# 56_ch_sample-and-hold_card_v1_1.net
KiCad netlist of a schematic drawn in EAGLE
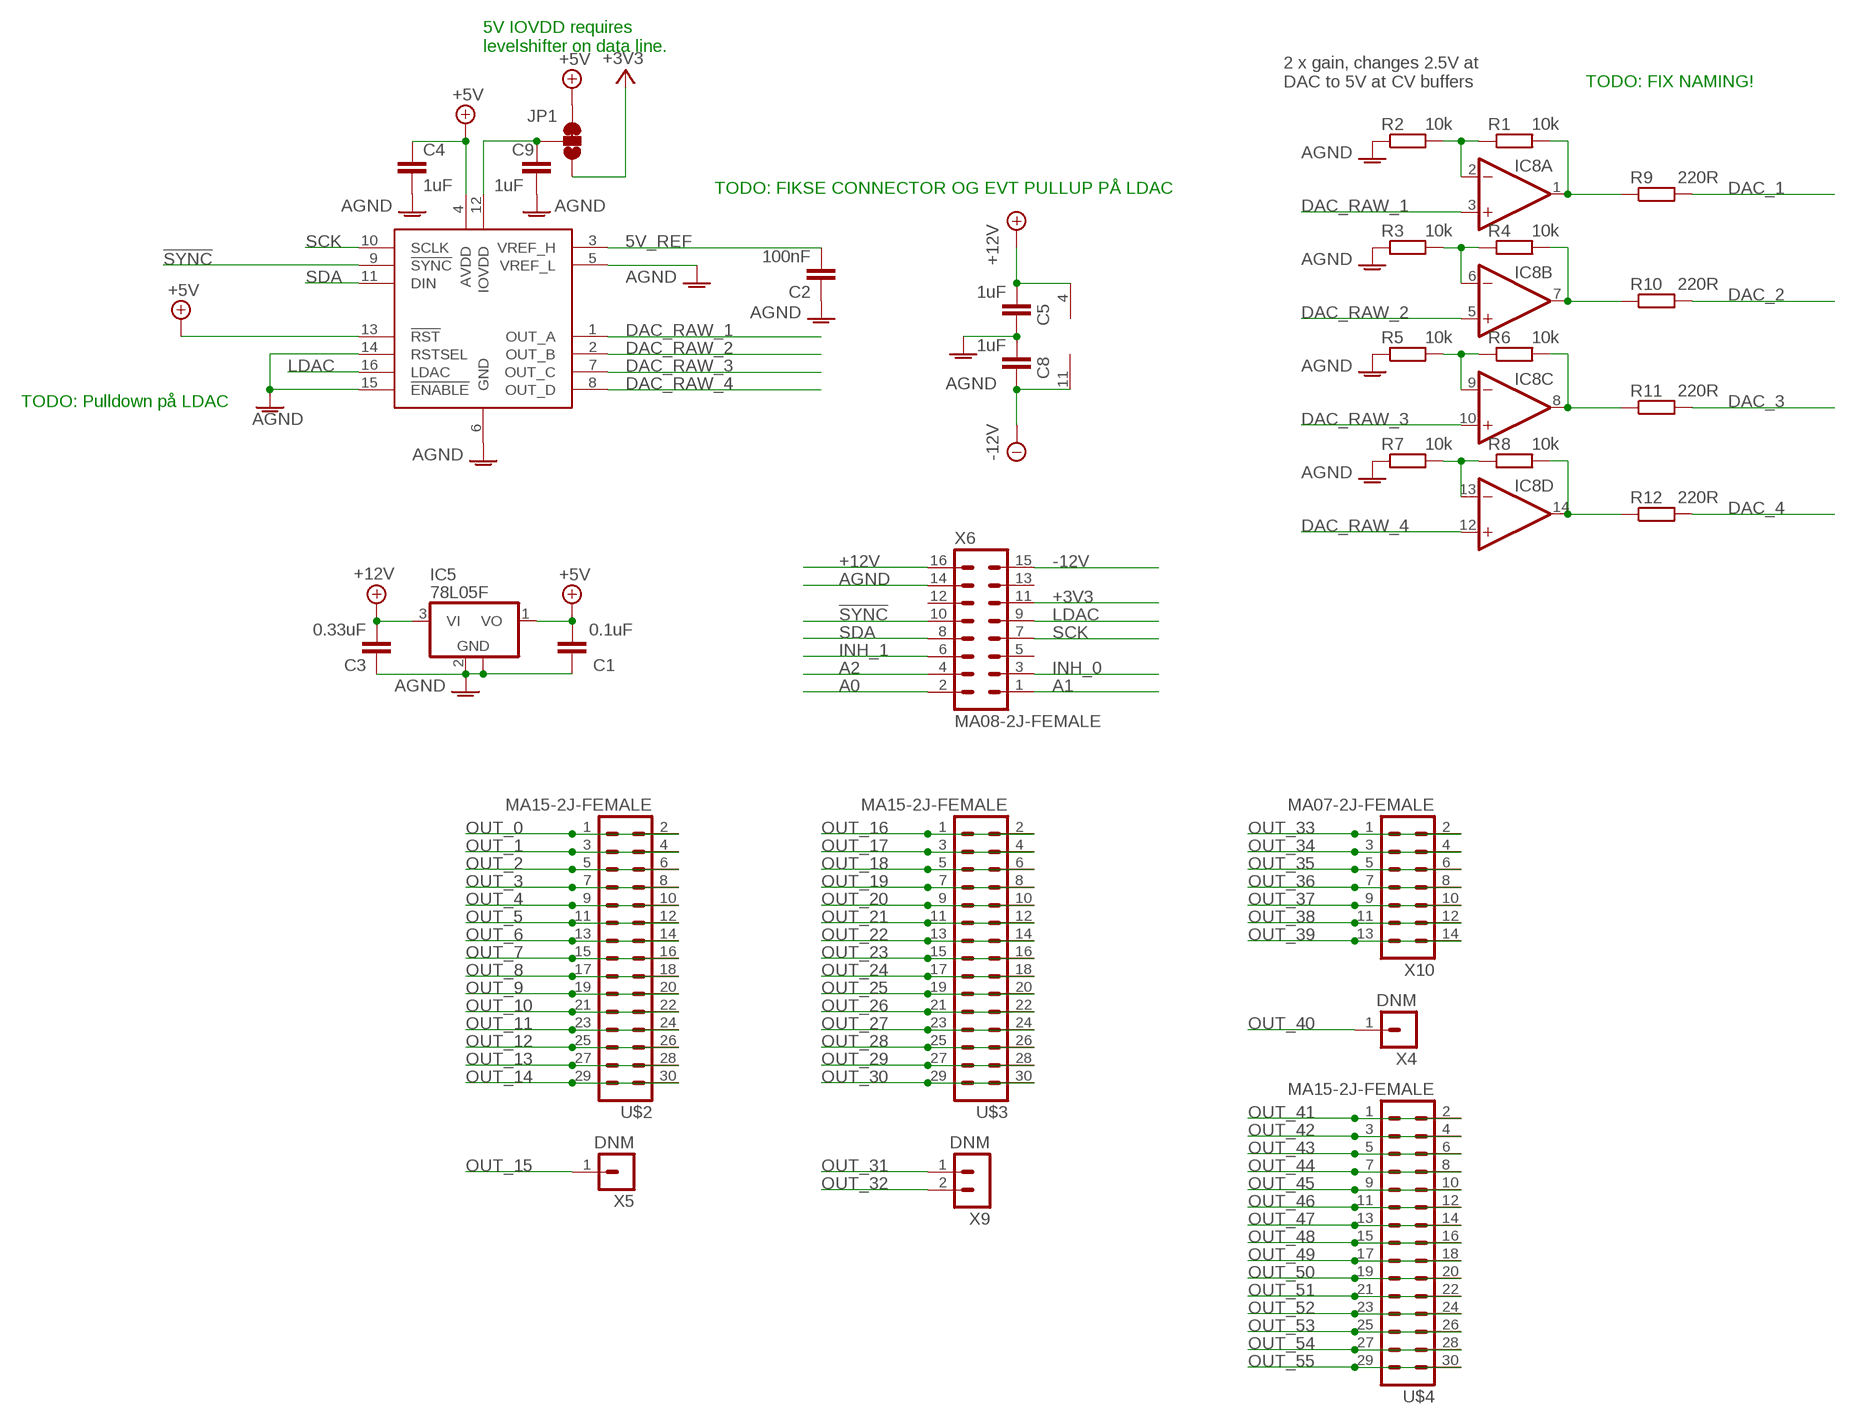
[diagram p0: schematic, sheet 1]
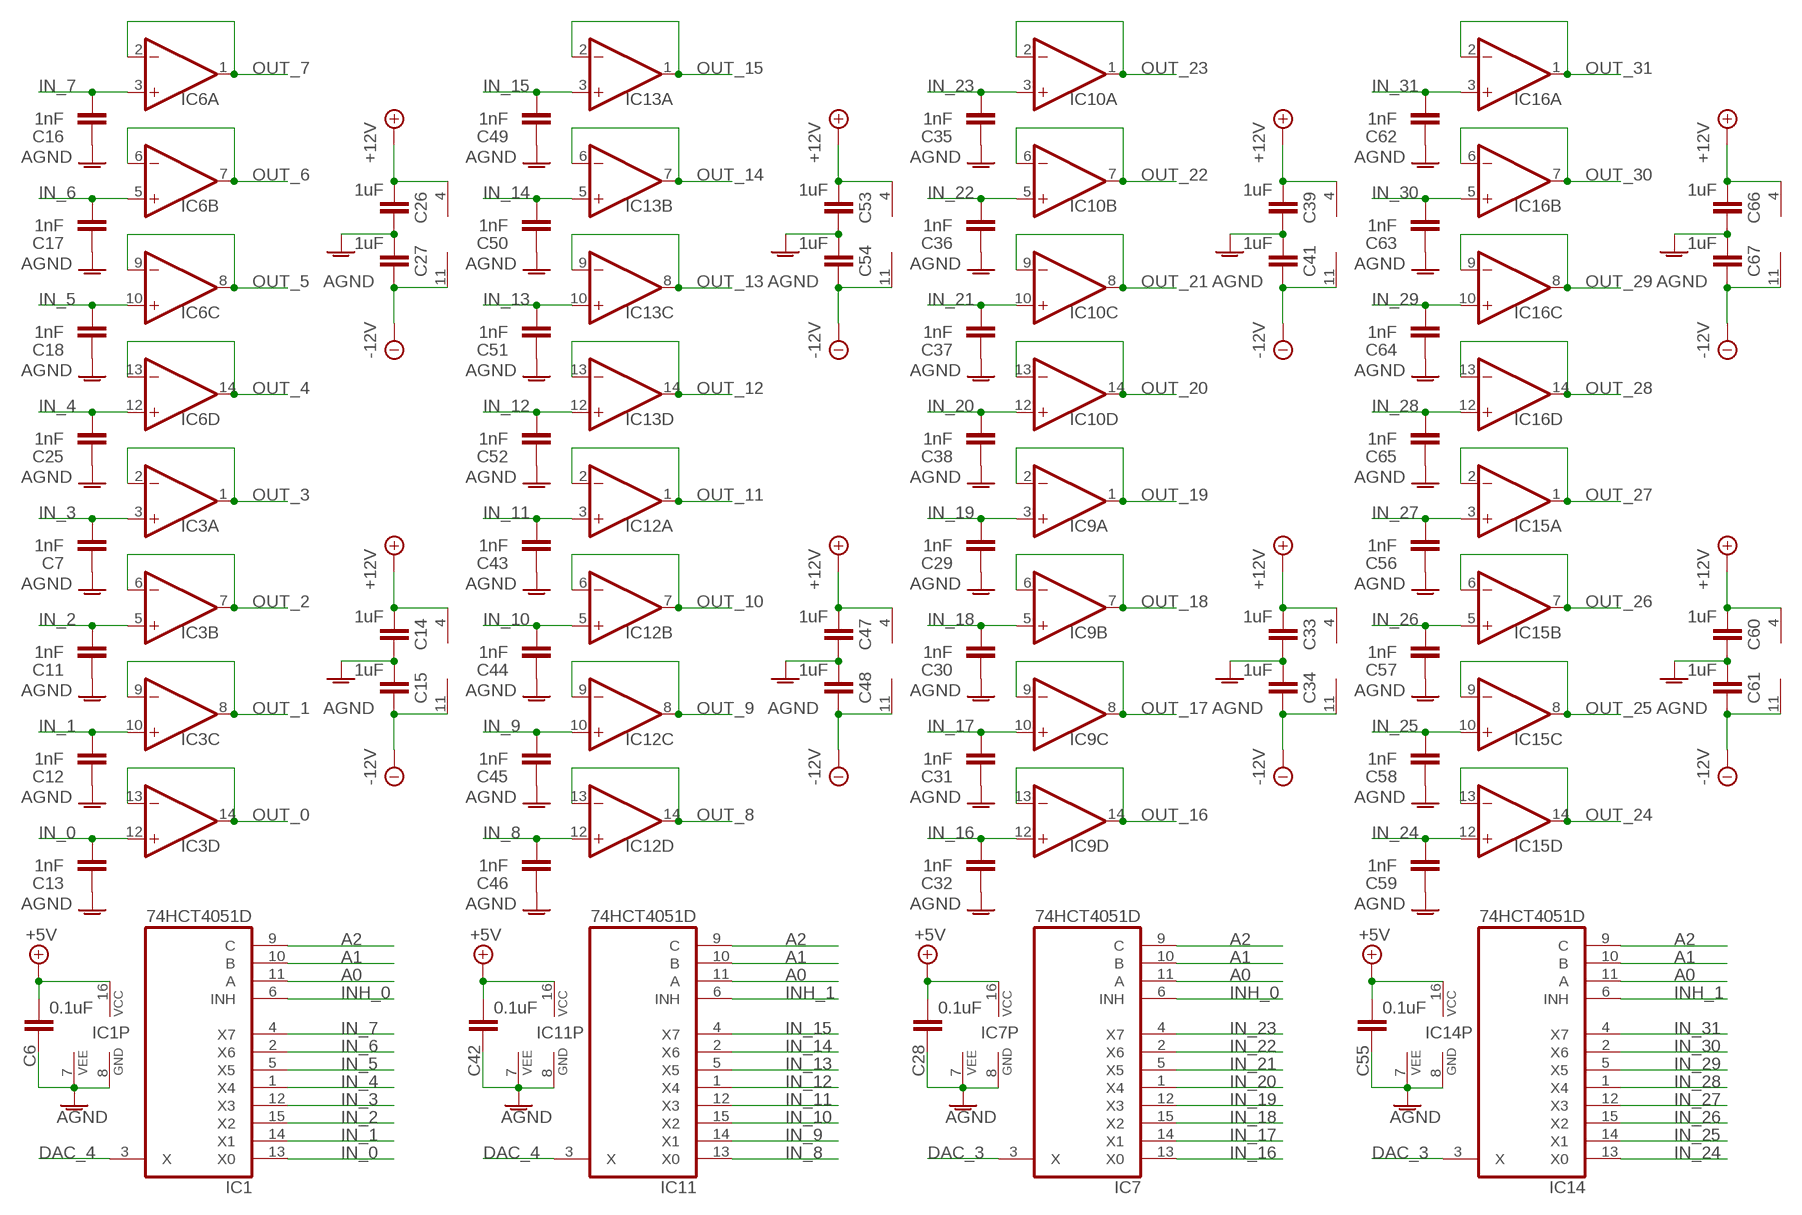
[diagram p1: schematic, sheet 2]
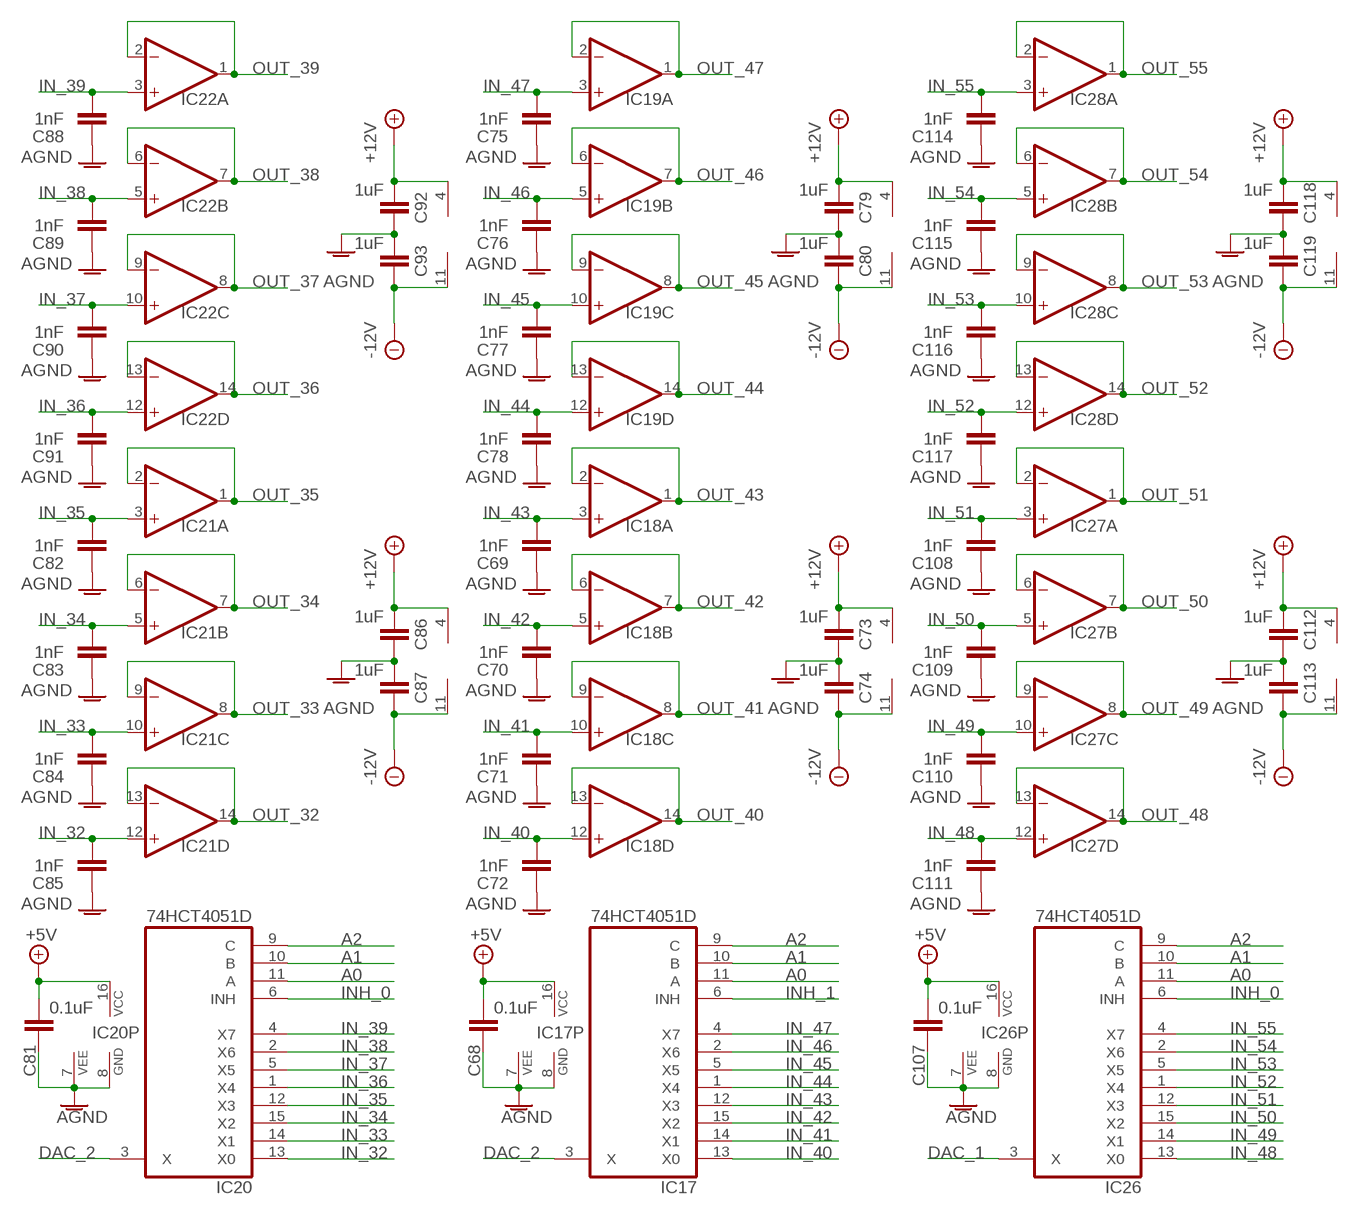
[diagram p2: schematic, sheet 3]

(export (version "E")
  (design (tool "Eeschema 10.0.6"))
  (components
    (comp (ref "C1")
      (value "0.1uF")
      (footprint "eagle-import:C0603")
      (libsource (lib "eagle-import") (part "C-EUC0603"))
    )
    (comp (ref "C2")
      (value "100nF")
      (footprint "eagle-import:C0603")
      (libsource (lib "eagle-import") (part "C-EUC0603"))
    )
    (comp (ref "C3")
      (value "0.33uF")
      (footprint "eagle-import:C0603")
      (libsource (lib "eagle-import") (part "C-EUC0603"))
    )
    (comp (ref "C4")
      (value "1uF")
      (footprint "eagle-import:C0402-J")
      (libsource (lib "eagle-import") (part "C-EU-J0402"))
    )
    (comp (ref "C5")
      (value "1uF")
      (footprint "eagle-import:C0402-J")
      (libsource (lib "eagle-import") (part "C-EU-J0402"))
    )
    (comp (ref "C8")
      (value "1uF")
      (footprint "eagle-import:C0402-J")
      (libsource (lib "eagle-import") (part "C-EU-J0402"))
    )
    (comp (ref "C9")
      (value "1uF")
      (footprint "eagle-import:C0402-J")
      (libsource (lib "eagle-import") (part "C-EU-J0402"))
    )
    (comp (ref "IC2")
      (value "DAC8565F")
      (footprint "eagle-import:DIL16-FM-CON")
      (libsource (lib "eagle-import") (part "DAC8565F"))
    )
    (comp (ref "IC5")
      (value "78L05F")
      (footprint "eagle-import:SOT89")
      (libsource (lib "eagle-import") (part "78LF05"))
    )
    (comp (ref "IC8")
      (value "TL074JT")
      (footprint "eagle-import:TSSOP14J")
      (libsource (lib "eagle-import") (part "TL074JT"))
    )
    (comp (ref "JP1")
      (value "JUMPER-SMT_3_1-NC_TRACE_NO-SILK_DNM")
      (footprint "eagle-import:SMT-JUMPER_3_1-NC_TRACE_NO-SILK")
      (libsource (lib "eagle-import") (part "JUMPER-SMT_3_1-NC_TRACE_NO-SILK"))
    )
    (comp (ref "R1")
      (value "10k")
      (footprint "eagle-import:R0603")
      (libsource (lib "eagle-import") (part "R-EU_R0603"))
    )
    (comp (ref "R2")
      (value "10k")
      (footprint "eagle-import:R0603")
      (libsource (lib "eagle-import") (part "R-EU_R0603"))
    )
    (comp (ref "R3")
      (value "10k")
      (footprint "eagle-import:R0603")
      (libsource (lib "eagle-import") (part "R-EU_R0603"))
    )
    (comp (ref "R4")
      (value "10k")
      (footprint "eagle-import:R0603")
      (libsource (lib "eagle-import") (part "R-EU_R0603"))
    )
    (comp (ref "R5")
      (value "10k")
      (footprint "eagle-import:R0603")
      (libsource (lib "eagle-import") (part "R-EU_R0603"))
    )
    (comp (ref "R6")
      (value "10k")
      (footprint "eagle-import:R0603")
      (libsource (lib "eagle-import") (part "R-EU_R0603"))
    )
    (comp (ref "R7")
      (value "10k")
      (footprint "eagle-import:R0603")
      (libsource (lib "eagle-import") (part "R-EU_R0603"))
    )
    (comp (ref "R8")
      (value "10k")
      (footprint "eagle-import:R0603")
      (libsource (lib "eagle-import") (part "R-EU_R0603"))
    )
    (comp (ref "R9")
      (value "220R")
      (footprint "eagle-import:R0603")
      (libsource (lib "eagle-import") (part "R-EU_R0603"))
    )
    (comp (ref "R10")
      (value "220R")
      (footprint "eagle-import:R0603")
      (libsource (lib "eagle-import") (part "R-EU_R0603"))
    )
    (comp (ref "R11")
      (value "220R")
      (footprint "eagle-import:R0603")
      (libsource (lib "eagle-import") (part "R-EU_R0603"))
    )
    (comp (ref "R12")
      (value "220R")
      (footprint "eagle-import:R0603")
      (libsource (lib "eagle-import") (part "R-EU_R0603"))
    )
    (comp (ref "U$2")
      (value "MA15-2J-FEMALE")
      (footprint "eagle-import:MA15-2J")
      (libsource (lib "eagle-import") (part "MA15-2J"))
    )
    (comp (ref "U$3")
      (value "MA15-2J-FEMALE")
      (footprint "eagle-import:MA15-2J")
      (libsource (lib "eagle-import") (part "MA15-2J"))
    )
    (comp (ref "U$4")
      (value "MA15-2J-FEMALE")
      (footprint "eagle-import:MA15-2J")
      (libsource (lib "eagle-import") (part "MA15-2J"))
    )
    (comp (ref "X4")
      (value "DNM")
      (footprint "eagle-import:MA01N-1J")
      (libsource (lib "eagle-import") (part "MA01-1JN"))
    )
    (comp (ref "X5")
      (value "DNM")
      (footprint "eagle-import:MA01N-1J")
      (libsource (lib "eagle-import") (part "MA01-1JN"))
    )
    (comp (ref "X6")
      (value "MA08-2J-FEMALE")
      (footprint "eagle-import:MA08-2J")
      (libsource (lib "eagle-import") (part "MA08-2J"))
    )
    (comp (ref "X9")
      (value "DNM")
      (footprint "eagle-import:MA02N-1J")
      (libsource (lib "eagle-import") (part "MA02-1JN"))
    )
    (comp (ref "X10")
      (value "MA07-2J-FEMALE")
      (footprint "eagle-import:MA07-2J")
      (libsource (lib "eagle-import") (part "MA07-2J"))
    )
    (comp (ref "C6")
      (value "0.1uF")
      (footprint "eagle-import:C0402-J")
      (libsource (lib "eagle-import") (part "C-EU-J0402"))
    )
    (comp (ref "C7")
      (value "1nF")
      (footprint "eagle-import:C0603-J")
      (libsource (lib "eagle-import") (part "C-EU-J0603"))
    )
    (comp (ref "C11")
      (value "1nF")
      (footprint "eagle-import:C0603-J")
      (libsource (lib "eagle-import") (part "C-EU-J0603"))
    )
    (comp (ref "C12")
      (value "1nF")
      (footprint "eagle-import:C0603-J")
      (libsource (lib "eagle-import") (part "C-EU-J0603"))
    )
    (comp (ref "C13")
      (value "1nF")
      (footprint "eagle-import:C0603-J")
      (libsource (lib "eagle-import") (part "C-EU-J0603"))
    )
    (comp (ref "C14")
      (value "1uF")
      (footprint "eagle-import:C0402-J")
      (libsource (lib "eagle-import") (part "C-EU-J0402"))
    )
    (comp (ref "C15")
      (value "1uF")
      (footprint "eagle-import:C0402-J")
      (libsource (lib "eagle-import") (part "C-EU-J0402"))
    )
    (comp (ref "C16")
      (value "1nF")
      (footprint "eagle-import:C0603-J")
      (libsource (lib "eagle-import") (part "C-EU-J0603"))
    )
    (comp (ref "C17")
      (value "1nF")
      (footprint "eagle-import:C0603-J")
      (libsource (lib "eagle-import") (part "C-EU-J0603"))
    )
    (comp (ref "C18")
      (value "1nF")
      (footprint "eagle-import:C0603-J")
      (libsource (lib "eagle-import") (part "C-EU-J0603"))
    )
    (comp (ref "C25")
      (value "1nF")
      (footprint "eagle-import:C0603-J")
      (libsource (lib "eagle-import") (part "C-EU-J0603"))
    )
    (comp (ref "C26")
      (value "1uF")
      (footprint "eagle-import:C0402-J")
      (libsource (lib "eagle-import") (part "C-EU-J0402"))
    )
    (comp (ref "C27")
      (value "1uF")
      (footprint "eagle-import:C0402-J")
      (libsource (lib "eagle-import") (part "C-EU-J0402"))
    )
    (comp (ref "C28")
      (value "0.1uF")
      (footprint "eagle-import:C0402-J")
      (libsource (lib "eagle-import") (part "C-EU-J0402"))
    )
    (comp (ref "C29")
      (value "1nF")
      (footprint "eagle-import:C0603-J")
      (libsource (lib "eagle-import") (part "C-EU-J0603"))
    )
    (comp (ref "C30")
      (value "1nF")
      (footprint "eagle-import:C0603-J")
      (libsource (lib "eagle-import") (part "C-EU-J0603"))
    )
    (comp (ref "C31")
      (value "1nF")
      (footprint "eagle-import:C0603-J")
      (libsource (lib "eagle-import") (part "C-EU-J0603"))
    )
    (comp (ref "C32")
      (value "1nF")
      (footprint "eagle-import:C0603-J")
      (libsource (lib "eagle-import") (part "C-EU-J0603"))
    )
    (comp (ref "C33")
      (value "1uF")
      (footprint "eagle-import:C0402-J")
      (libsource (lib "eagle-import") (part "C-EU-J0402"))
    )
    (comp (ref "C34")
      (value "1uF")
      (footprint "eagle-import:C0402-J")
      (libsource (lib "eagle-import") (part "C-EU-J0402"))
    )
    (comp (ref "C35")
      (value "1nF")
      (footprint "eagle-import:C0603-J")
      (libsource (lib "eagle-import") (part "C-EU-J0603"))
    )
    (comp (ref "C36")
      (value "1nF")
      (footprint "eagle-import:C0603-J")
      (libsource (lib "eagle-import") (part "C-EU-J0603"))
    )
    (comp (ref "C37")
      (value "1nF")
      (footprint "eagle-import:C0603-J")
      (libsource (lib "eagle-import") (part "C-EU-J0603"))
    )
    (comp (ref "C38")
      (value "1nF")
      (footprint "eagle-import:C0603-J")
      (libsource (lib "eagle-import") (part "C-EU-J0603"))
    )
    (comp (ref "C39")
      (value "1uF")
      (footprint "eagle-import:C0402-J")
      (libsource (lib "eagle-import") (part "C-EU-J0402"))
    )
    (comp (ref "C41")
      (value "1uF")
      (footprint "eagle-import:C0402-J")
      (libsource (lib "eagle-import") (part "C-EU-J0402"))
    )
    (comp (ref "C42")
      (value "0.1uF")
      (footprint "eagle-import:C0402-J")
      (libsource (lib "eagle-import") (part "C-EU-J0402"))
    )
    (comp (ref "C43")
      (value "1nF")
      (footprint "eagle-import:C0603-J")
      (libsource (lib "eagle-import") (part "C-EU-J0603"))
    )
    (comp (ref "C44")
      (value "1nF")
      (footprint "eagle-import:C0603-J")
      (libsource (lib "eagle-import") (part "C-EU-J0603"))
    )
    (comp (ref "C45")
      (value "1nF")
      (footprint "eagle-import:C0603-J")
      (libsource (lib "eagle-import") (part "C-EU-J0603"))
    )
    (comp (ref "C46")
      (value "1nF")
      (footprint "eagle-import:C0603-J")
      (libsource (lib "eagle-import") (part "C-EU-J0603"))
    )
    (comp (ref "C47")
      (value "1uF")
      (footprint "eagle-import:C0402-J")
      (libsource (lib "eagle-import") (part "C-EU-J0402"))
    )
    (comp (ref "C48")
      (value "1uF")
      (footprint "eagle-import:C0402-J")
      (libsource (lib "eagle-import") (part "C-EU-J0402"))
    )
    (comp (ref "C49")
      (value "1nF")
      (footprint "eagle-import:C0603-J")
      (libsource (lib "eagle-import") (part "C-EU-J0603"))
    )
    (comp (ref "C50")
      (value "1nF")
      (footprint "eagle-import:C0603-J")
      (libsource (lib "eagle-import") (part "C-EU-J0603"))
    )
    (comp (ref "C51")
      (value "1nF")
      (footprint "eagle-import:C0603-J")
      (libsource (lib "eagle-import") (part "C-EU-J0603"))
    )
    (comp (ref "C52")
      (value "1nF")
      (footprint "eagle-import:C0603-J")
      (libsource (lib "eagle-import") (part "C-EU-J0603"))
    )
    (comp (ref "C53")
      (value "1uF")
      (footprint "eagle-import:C0402-J")
      (libsource (lib "eagle-import") (part "C-EU-J0402"))
    )
    (comp (ref "C54")
      (value "1uF")
      (footprint "eagle-import:C0402-J")
      (libsource (lib "eagle-import") (part "C-EU-J0402"))
    )
    (comp (ref "C55")
      (value "0.1uF")
      (footprint "eagle-import:C0402-J")
      (libsource (lib "eagle-import") (part "C-EU-J0402"))
    )
    (comp (ref "C56")
      (value "1nF")
      (footprint "eagle-import:C0603-J")
      (libsource (lib "eagle-import") (part "C-EU-J0603"))
    )
    (comp (ref "C57")
      (value "1nF")
      (footprint "eagle-import:C0603-J")
      (libsource (lib "eagle-import") (part "C-EU-J0603"))
    )
    (comp (ref "C58")
      (value "1nF")
      (footprint "eagle-import:C0603-J")
      (libsource (lib "eagle-import") (part "C-EU-J0603"))
    )
    (comp (ref "C59")
      (value "1nF")
      (footprint "eagle-import:C0603-J")
      (libsource (lib "eagle-import") (part "C-EU-J0603"))
    )
    (comp (ref "C60")
      (value "1uF")
      (footprint "eagle-import:C0402-J")
      (libsource (lib "eagle-import") (part "C-EU-J0402"))
    )
    (comp (ref "C61")
      (value "1uF")
      (footprint "eagle-import:C0402-J")
      (libsource (lib "eagle-import") (part "C-EU-J0402"))
    )
    (comp (ref "C62")
      (value "1nF")
      (footprint "eagle-import:C0603-J")
      (libsource (lib "eagle-import") (part "C-EU-J0603"))
    )
    (comp (ref "C63")
      (value "1nF")
      (footprint "eagle-import:C0603-J")
      (libsource (lib "eagle-import") (part "C-EU-J0603"))
    )
    (comp (ref "C64")
      (value "1nF")
      (footprint "eagle-import:C0603-J")
      (libsource (lib "eagle-import") (part "C-EU-J0603"))
    )
    (comp (ref "C65")
      (value "1nF")
      (footprint "eagle-import:C0603-J")
      (libsource (lib "eagle-import") (part "C-EU-J0603"))
    )
    (comp (ref "C66")
      (value "1uF")
      (footprint "eagle-import:C0402-J")
      (libsource (lib "eagle-import") (part "C-EU-J0402"))
    )
    (comp (ref "C67")
      (value "1uF")
      (footprint "eagle-import:C0402-J")
      (libsource (lib "eagle-import") (part "C-EU-J0402"))
    )
    (comp (ref "IC1")
      (value "74HCT4051D")
      (footprint "eagle-import:SO16")
      (libsource (lib "eagle-import") (part "4051D"))
    )
    (comp (ref "IC3")
      (value "TL074JT")
      (footprint "eagle-import:TSSOP14J")
      (libsource (lib "eagle-import") (part "TL074JT"))
    )
    (comp (ref "IC6")
      (value "TL074JT")
      (footprint "eagle-import:TSSOP14J")
      (libsource (lib "eagle-import") (part "TL074JT"))
    )
    (comp (ref "IC7")
      (value "74HCT4051D")
      (footprint "eagle-import:SO16")
      (libsource (lib "eagle-import") (part "4051D"))
    )
    (comp (ref "IC9")
      (value "TL074JT")
      (footprint "eagle-import:TSSOP14J")
      (libsource (lib "eagle-import") (part "TL074JT"))
    )
    (comp (ref "IC10")
      (value "TL074JT")
      (footprint "eagle-import:TSSOP14J")
      (libsource (lib "eagle-import") (part "TL074JT"))
    )
    (comp (ref "IC11")
      (value "74HCT4051D")
      (footprint "eagle-import:SO16")
      (libsource (lib "eagle-import") (part "4051D"))
    )
    (comp (ref "IC12")
      (value "TL074JT")
      (footprint "eagle-import:TSSOP14J")
      (libsource (lib "eagle-import") (part "TL074JT"))
    )
    (comp (ref "IC13")
      (value "TL074JT")
      (footprint "eagle-import:TSSOP14J")
      (libsource (lib "eagle-import") (part "TL074JT"))
    )
    (comp (ref "IC14")
      (value "74HCT4051D")
      (footprint "eagle-import:SO16")
      (libsource (lib "eagle-import") (part "4051D"))
    )
    (comp (ref "IC15")
      (value "TL074JT")
      (footprint "eagle-import:TSSOP14J")
      (libsource (lib "eagle-import") (part "TL074JT"))
    )
    (comp (ref "IC16")
      (value "TL074JT")
      (footprint "eagle-import:TSSOP14J")
      (libsource (lib "eagle-import") (part "TL074JT"))
    )
    (comp (ref "C68")
      (value "0.1uF")
      (footprint "eagle-import:C0402-J")
      (libsource (lib "eagle-import") (part "C-EU-J0402"))
    )
    (comp (ref "C69")
      (value "1nF")
      (footprint "eagle-import:C0603-J")
      (libsource (lib "eagle-import") (part "C-EU-J0603"))
    )
    (comp (ref "C70")
      (value "1nF")
      (footprint "eagle-import:C0603-J")
      (libsource (lib "eagle-import") (part "C-EU-J0603"))
    )
    (comp (ref "C71")
      (value "1nF")
      (footprint "eagle-import:C0603-J")
      (libsource (lib "eagle-import") (part "C-EU-J0603"))
    )
    (comp (ref "C72")
      (value "1nF")
      (footprint "eagle-import:C0603-J")
      (libsource (lib "eagle-import") (part "C-EU-J0603"))
    )
    (comp (ref "C73")
      (value "1uF")
      (footprint "eagle-import:C0402-J")
      (libsource (lib "eagle-import") (part "C-EU-J0402"))
    )
    (comp (ref "C74")
      (value "1uF")
      (footprint "eagle-import:C0402-J")
      (libsource (lib "eagle-import") (part "C-EU-J0402"))
    )
    (comp (ref "C75")
      (value "1nF")
      (footprint "eagle-import:C0603-J")
      (libsource (lib "eagle-import") (part "C-EU-J0603"))
    )
    (comp (ref "C76")
      (value "1nF")
      (footprint "eagle-import:C0603-J")
      (libsource (lib "eagle-import") (part "C-EU-J0603"))
    )
    (comp (ref "C77")
      (value "1nF")
      (footprint "eagle-import:C0603-J")
      (libsource (lib "eagle-import") (part "C-EU-J0603"))
    )
    (comp (ref "C78")
      (value "1nF")
      (footprint "eagle-import:C0603-J")
      (libsource (lib "eagle-import") (part "C-EU-J0603"))
    )
    (comp (ref "C79")
      (value "1uF")
      (footprint "eagle-import:C0402-J")
      (libsource (lib "eagle-import") (part "C-EU-J0402"))
    )
    (comp (ref "C80")
      (value "1uF")
      (footprint "eagle-import:C0402-J")
      (libsource (lib "eagle-import") (part "C-EU-J0402"))
    )
    (comp (ref "C81")
      (value "0.1uF")
      (footprint "eagle-import:C0402-J")
      (libsource (lib "eagle-import") (part "C-EU-J0402"))
    )
    (comp (ref "C82")
      (value "1nF")
      (footprint "eagle-import:C0603-J")
      (libsource (lib "eagle-import") (part "C-EU-J0603"))
    )
    (comp (ref "C83")
      (value "1nF")
      (footprint "eagle-import:C0603-J")
      (libsource (lib "eagle-import") (part "C-EU-J0603"))
    )
    (comp (ref "C84")
      (value "1nF")
      (footprint "eagle-import:C0603-J")
      (libsource (lib "eagle-import") (part "C-EU-J0603"))
    )
    (comp (ref "C85")
      (value "1nF")
      (footprint "eagle-import:C0603-J")
      (libsource (lib "eagle-import") (part "C-EU-J0603"))
    )
    (comp (ref "C86")
      (value "1uF")
      (footprint "eagle-import:C0402-J")
      (libsource (lib "eagle-import") (part "C-EU-J0402"))
    )
    (comp (ref "C87")
      (value "1uF")
      (footprint "eagle-import:C0402-J")
      (libsource (lib "eagle-import") (part "C-EU-J0402"))
    )
    (comp (ref "C88")
      (value "1nF")
      (footprint "eagle-import:C0603-J")
      (libsource (lib "eagle-import") (part "C-EU-J0603"))
    )
    (comp (ref "C89")
      (value "1nF")
      (footprint "eagle-import:C0603-J")
      (libsource (lib "eagle-import") (part "C-EU-J0603"))
    )
    (comp (ref "C90")
      (value "1nF")
      (footprint "eagle-import:C0603-J")
      (libsource (lib "eagle-import") (part "C-EU-J0603"))
    )
    (comp (ref "C91")
      (value "1nF")
      (footprint "eagle-import:C0603-J")
      (libsource (lib "eagle-import") (part "C-EU-J0603"))
    )
    (comp (ref "C92")
      (value "1uF")
      (footprint "eagle-import:C0402-J")
      (libsource (lib "eagle-import") (part "C-EU-J0402"))
    )
    (comp (ref "C93")
      (value "1uF")
      (footprint "eagle-import:C0402-J")
      (libsource (lib "eagle-import") (part "C-EU-J0402"))
    )
    (comp (ref "C107")
      (value "0.1uF")
      (footprint "eagle-import:C0402-J")
      (libsource (lib "eagle-import") (part "C-EU-J0402"))
    )
    (comp (ref "C108")
      (value "1nF")
      (footprint "eagle-import:C0603-J")
      (libsource (lib "eagle-import") (part "C-EU-J0603"))
    )
    (comp (ref "C109")
      (value "1nF")
      (footprint "eagle-import:C0603-J")
      (libsource (lib "eagle-import") (part "C-EU-J0603"))
    )
    (comp (ref "C110")
      (value "1nF")
      (footprint "eagle-import:C0603-J")
      (libsource (lib "eagle-import") (part "C-EU-J0603"))
    )
    (comp (ref "C111")
      (value "1nF")
      (footprint "eagle-import:C0603-J")
      (libsource (lib "eagle-import") (part "C-EU-J0603"))
    )
    (comp (ref "C112")
      (value "1uF")
      (footprint "eagle-import:C0402-J")
      (libsource (lib "eagle-import") (part "C-EU-J0402"))
    )
    (comp (ref "C113")
      (value "1uF")
      (footprint "eagle-import:C0402-J")
      (libsource (lib "eagle-import") (part "C-EU-J0402"))
    )
    (comp (ref "C114")
      (value "1nF")
      (footprint "eagle-import:C0603-J")
      (libsource (lib "eagle-import") (part "C-EU-J0603"))
    )
    (comp (ref "C115")
      (value "1nF")
      (footprint "eagle-import:C0603-J")
      (libsource (lib "eagle-import") (part "C-EU-J0603"))
    )
    (comp (ref "C116")
      (value "1nF")
      (footprint "eagle-import:C0603-J")
      (libsource (lib "eagle-import") (part "C-EU-J0603"))
    )
    (comp (ref "C117")
      (value "1nF")
      (footprint "eagle-import:C0603-J")
      (libsource (lib "eagle-import") (part "C-EU-J0603"))
    )
    (comp (ref "C118")
      (value "1uF")
      (footprint "eagle-import:C0402-J")
      (libsource (lib "eagle-import") (part "C-EU-J0402"))
    )
    (comp (ref "C119")
      (value "1uF")
      (footprint "eagle-import:C0402-J")
      (libsource (lib "eagle-import") (part "C-EU-J0402"))
    )
    (comp (ref "IC17")
      (value "74HCT4051D")
      (footprint "eagle-import:SO16")
      (libsource (lib "eagle-import") (part "4051D"))
    )
    (comp (ref "IC18")
      (value "TL074JT")
      (footprint "eagle-import:TSSOP14J")
      (libsource (lib "eagle-import") (part "TL074JT"))
    )
    (comp (ref "IC19")
      (value "TL074JT")
      (footprint "eagle-import:TSSOP14J")
      (libsource (lib "eagle-import") (part "TL074JT"))
    )
    (comp (ref "IC20")
      (value "74HCT4051D")
      (footprint "eagle-import:SO16")
      (libsource (lib "eagle-import") (part "4051D"))
    )
    (comp (ref "IC21")
      (value "TL074JT")
      (footprint "eagle-import:TSSOP14J")
      (libsource (lib "eagle-import") (part "TL074JT"))
    )
    (comp (ref "IC22")
      (value "TL074JT")
      (footprint "eagle-import:TSSOP14J")
      (libsource (lib "eagle-import") (part "TL074JT"))
    )
    (comp (ref "IC26")
      (value "74HCT4051D")
      (footprint "eagle-import:SO16")
      (libsource (lib "eagle-import") (part "4051D"))
    )
    (comp (ref "IC27")
      (value "TL074JT")
      (footprint "eagle-import:TSSOP14J")
      (libsource (lib "eagle-import") (part "TL074JT"))
    )
    (comp (ref "IC28")
      (value "TL074JT")
      (footprint "eagle-import:TSSOP14J")
      (libsource (lib "eagle-import") (part "TL074JT"))
    )
  )
  (nets
    (net (code "1") (name "+3V3") (class "Default")
      (node (ref "JP1") (pin "1") (pinfunction "1_1") (pintype "passive"))
      (node (ref "X6") (pin "11") (pinfunction "11_11") (pintype "passive"))
    )
    (net (code "2") (name "+5V") (class "Default")
      (node (ref "C1") (pin "2") (pinfunction "2_2") (pintype "passive"))
      (node (ref "C107") (pin "2") (pinfunction "2_2") (pintype "passive"))
      (node (ref "C28") (pin "2") (pinfunction "2_2") (pintype "passive"))
      (node (ref "C4") (pin "1") (pinfunction "1_1") (pintype "passive"))
      (node (ref "C42") (pin "2") (pinfunction "2_2") (pintype "passive"))
      (node (ref "C55") (pin "2") (pinfunction "2_2") (pintype "passive"))
      (node (ref "C6") (pin "2") (pinfunction "2_2") (pintype "passive"))
      (node (ref "C68") (pin "2") (pinfunction "2_2") (pintype "passive"))
      (node (ref "C81") (pin "2") (pinfunction "2_2") (pintype "passive"))
      (node (ref "IC1") (pin "16") (pinfunction "VCC_16") (pintype "power_in"))
      (node (ref "IC11") (pin "16") (pinfunction "VCC_16") (pintype "power_in"))
      (node (ref "IC14") (pin "16") (pinfunction "VCC_16") (pintype "power_in"))
      (node (ref "IC17") (pin "16") (pinfunction "VCC_16") (pintype "power_in"))
      (node (ref "IC2") (pin "13") (pinfunction "~{RST}_13") (pintype "bidirectional"))
      (node (ref "IC2") (pin "4") (pinfunction "AVDD_4") (pintype "power_in"))
      (node (ref "IC20") (pin "16") (pinfunction "VCC_16") (pintype "power_in"))
      (node (ref "IC26") (pin "16") (pinfunction "VCC_16") (pintype "power_in"))
      (node (ref "IC5") (pin "1") (pinfunction "VO_1") (pintype "passive"))
      (node (ref "IC7") (pin "16") (pinfunction "VCC_16") (pintype "power_in"))
      (node (ref "JP1") (pin "3") (pinfunction "3_3") (pintype "passive"))
    )
    (net (code "3") (name "+12V") (class "Default")
      (node (ref "C112") (pin "1") (pinfunction "1_1") (pintype "passive"))
      (node (ref "C118") (pin "1") (pinfunction "1_1") (pintype "passive"))
      (node (ref "C14") (pin "1") (pinfunction "1_1") (pintype "passive"))
      (node (ref "C26") (pin "1") (pinfunction "1_1") (pintype "passive"))
      (node (ref "C3") (pin "2") (pinfunction "2_2") (pintype "passive"))
      (node (ref "C33") (pin "1") (pinfunction "1_1") (pintype "passive"))
      (node (ref "C39") (pin "1") (pinfunction "1_1") (pintype "passive"))
      (node (ref "C47") (pin "1") (pinfunction "1_1") (pintype "passive"))
      (node (ref "C5") (pin "1") (pinfunction "1_1") (pintype "passive"))
      (node (ref "C53") (pin "1") (pinfunction "1_1") (pintype "passive"))
      (node (ref "C60") (pin "1") (pinfunction "1_1") (pintype "passive"))
      (node (ref "C66") (pin "1") (pinfunction "1_1") (pintype "passive"))
      (node (ref "C73") (pin "1") (pinfunction "1_1") (pintype "passive"))
      (node (ref "C79") (pin "1") (pinfunction "1_1") (pintype "passive"))
      (node (ref "C86") (pin "1") (pinfunction "1_1") (pintype "passive"))
      (node (ref "C92") (pin "1") (pinfunction "1_1") (pintype "passive"))
      (node (ref "IC10") (pin "4") (pinfunction "V+_4") (pintype "power_in"))
      (node (ref "IC12") (pin "4") (pinfunction "V+_4") (pintype "power_in"))
      (node (ref "IC13") (pin "4") (pinfunction "V+_4") (pintype "power_in"))
      (node (ref "IC15") (pin "4") (pinfunction "V+_4") (pintype "power_in"))
      (node (ref "IC16") (pin "4") (pinfunction "V+_4") (pintype "power_in"))
      (node (ref "IC18") (pin "4") (pinfunction "V+_4") (pintype "power_in"))
      (node (ref "IC19") (pin "4") (pinfunction "V+_4") (pintype "power_in"))
      (node (ref "IC21") (pin "4") (pinfunction "V+_4") (pintype "power_in"))
      (node (ref "IC22") (pin "4") (pinfunction "V+_4") (pintype "power_in"))
      (node (ref "IC27") (pin "4") (pinfunction "V+_4") (pintype "power_in"))
      (node (ref "IC28") (pin "4") (pinfunction "V+_4") (pintype "power_in"))
      (node (ref "IC3") (pin "4") (pinfunction "V+_4") (pintype "power_in"))
      (node (ref "IC5") (pin "3") (pinfunction "VI_3") (pintype "input"))
      (node (ref "IC6") (pin "4") (pinfunction "V+_4") (pintype "power_in"))
      (node (ref "IC8") (pin "4") (pinfunction "V+_4") (pintype "power_in"))
      (node (ref "IC9") (pin "4") (pinfunction "V+_4") (pintype "power_in"))
      (node (ref "X6") (pin "16") (pinfunction "16_16") (pintype "passive"))
    )
    (net (code "4") (name "-12V") (class "Default")
      (node (ref "C113") (pin "2") (pinfunction "2_2") (pintype "passive"))
      (node (ref "C119") (pin "2") (pinfunction "2_2") (pintype "passive"))
      (node (ref "C15") (pin "2") (pinfunction "2_2") (pintype "passive"))
      (node (ref "C27") (pin "2") (pinfunction "2_2") (pintype "passive"))
      (node (ref "C34") (pin "2") (pinfunction "2_2") (pintype "passive"))
      (node (ref "C41") (pin "2") (pinfunction "2_2") (pintype "passive"))
      (node (ref "C48") (pin "2") (pinfunction "2_2") (pintype "passive"))
      (node (ref "C54") (pin "2") (pinfunction "2_2") (pintype "passive"))
      (node (ref "C61") (pin "2") (pinfunction "2_2") (pintype "passive"))
      (node (ref "C67") (pin "2") (pinfunction "2_2") (pintype "passive"))
      (node (ref "C74") (pin "2") (pinfunction "2_2") (pintype "passive"))
      (node (ref "C8") (pin "2") (pinfunction "2_2") (pintype "passive"))
      (node (ref "C80") (pin "2") (pinfunction "2_2") (pintype "passive"))
      (node (ref "C87") (pin "2") (pinfunction "2_2") (pintype "passive"))
      (node (ref "C93") (pin "2") (pinfunction "2_2") (pintype "passive"))
      (node (ref "IC10") (pin "11") (pinfunction "V-_11") (pintype "power_in"))
      (node (ref "IC12") (pin "11") (pinfunction "V-_11") (pintype "power_in"))
      (node (ref "IC13") (pin "11") (pinfunction "V-_11") (pintype "power_in"))
      (node (ref "IC15") (pin "11") (pinfunction "V-_11") (pintype "power_in"))
      (node (ref "IC16") (pin "11") (pinfunction "V-_11") (pintype "power_in"))
      (node (ref "IC18") (pin "11") (pinfunction "V-_11") (pintype "power_in"))
      (node (ref "IC19") (pin "11") (pinfunction "V-_11") (pintype "power_in"))
      (node (ref "IC21") (pin "11") (pinfunction "V-_11") (pintype "power_in"))
      (node (ref "IC22") (pin "11") (pinfunction "V-_11") (pintype "power_in"))
      (node (ref "IC27") (pin "11") (pinfunction "V-_11") (pintype "power_in"))
      (node (ref "IC28") (pin "11") (pinfunction "V-_11") (pintype "power_in"))
      (node (ref "IC3") (pin "11") (pinfunction "V-_11") (pintype "power_in"))
      (node (ref "IC6") (pin "11") (pinfunction "V-_11") (pintype "power_in"))
      (node (ref "IC8") (pin "11") (pinfunction "V-_11") (pintype "power_in"))
      (node (ref "IC9") (pin "11") (pinfunction "V-_11") (pintype "power_in"))
      (node (ref "X6") (pin "15") (pinfunction "15_15") (pintype "passive"))
    )
    (net (code "5") (name "5V_REF") (class "Default")
      (node (ref "C2") (pin "2") (pinfunction "2_2") (pintype "passive"))
      (node (ref "IC2") (pin "3") (pinfunction "VREF_H_3") (pintype "bidirectional"))
    )
    (net (code "6") (name "A0") (class "Default")
      (node (ref "IC1") (pin "11") (pinfunction "A_11") (pintype "input"))
      (node (ref "IC11") (pin "11") (pinfunction "A_11") (pintype "input"))
      (node (ref "IC14") (pin "11") (pinfunction "A_11") (pintype "input"))
      (node (ref "IC17") (pin "11") (pinfunction "A_11") (pintype "input"))
      (node (ref "IC20") (pin "11") (pinfunction "A_11") (pintype "input"))
      (node (ref "IC26") (pin "11") (pinfunction "A_11") (pintype "input"))
      (node (ref "IC7") (pin "11") (pinfunction "A_11") (pintype "input"))
      (node (ref "X6") (pin "2") (pinfunction "2_2") (pintype "passive"))
    )
    (net (code "7") (name "A1") (class "Default")
      (node (ref "IC1") (pin "10") (pinfunction "B_10") (pintype "input"))
      (node (ref "IC11") (pin "10") (pinfunction "B_10") (pintype "input"))
      (node (ref "IC14") (pin "10") (pinfunction "B_10") (pintype "input"))
      (node (ref "IC17") (pin "10") (pinfunction "B_10") (pintype "input"))
      (node (ref "IC20") (pin "10") (pinfunction "B_10") (pintype "input"))
      (node (ref "IC26") (pin "10") (pinfunction "B_10") (pintype "input"))
      (node (ref "IC7") (pin "10") (pinfunction "B_10") (pintype "input"))
      (node (ref "X6") (pin "1") (pinfunction "1_1") (pintype "passive"))
    )
    (net (code "8") (name "A2") (class "Default")
      (node (ref "IC1") (pin "9") (pinfunction "C_9") (pintype "input"))
      (node (ref "IC11") (pin "9") (pinfunction "C_9") (pintype "input"))
      (node (ref "IC14") (pin "9") (pinfunction "C_9") (pintype "input"))
      (node (ref "IC17") (pin "9") (pinfunction "C_9") (pintype "input"))
      (node (ref "IC20") (pin "9") (pinfunction "C_9") (pintype "input"))
      (node (ref "IC26") (pin "9") (pinfunction "C_9") (pintype "input"))
      (node (ref "IC7") (pin "9") (pinfunction "C_9") (pintype "input"))
      (node (ref "X6") (pin "4") (pinfunction "4_4") (pintype "passive"))
    )
    (net (code "9") (name "AGND") (class "Default")
      (node (ref "C1") (pin "1") (pinfunction "1_1") (pintype "passive"))
      (node (ref "C107") (pin "1") (pinfunction "1_1") (pintype "passive"))
      (node (ref "C108") (pin "1") (pinfunction "1_1") (pintype "passive"))
      (node (ref "C109") (pin "1") (pinfunction "1_1") (pintype "passive"))
      (node (ref "C11") (pin "1") (pinfunction "1_1") (pintype "passive"))
      (node (ref "C110") (pin "1") (pinfunction "1_1") (pintype "passive"))
      (node (ref "C111") (pin "1") (pinfunction "1_1") (pintype "passive"))
      (node (ref "C112") (pin "2") (pinfunction "2_2") (pintype "passive"))
      (node (ref "C113") (pin "1") (pinfunction "1_1") (pintype "passive"))
      (node (ref "C114") (pin "1") (pinfunction "1_1") (pintype "passive"))
      (node (ref "C115") (pin "1") (pinfunction "1_1") (pintype "passive"))
      (node (ref "C116") (pin "1") (pinfunction "1_1") (pintype "passive"))
      (node (ref "C117") (pin "1") (pinfunction "1_1") (pintype "passive"))
      (node (ref "C118") (pin "2") (pinfunction "2_2") (pintype "passive"))
      (node (ref "C119") (pin "1") (pinfunction "1_1") (pintype "passive"))
      (node (ref "C12") (pin "1") (pinfunction "1_1") (pintype "passive"))
      (node (ref "C13") (pin "1") (pinfunction "1_1") (pintype "passive"))
      (node (ref "C14") (pin "2") (pinfunction "2_2") (pintype "passive"))
      (node (ref "C15") (pin "1") (pinfunction "1_1") (pintype "passive"))
      (node (ref "C16") (pin "1") (pinfunction "1_1") (pintype "passive"))
      (node (ref "C17") (pin "1") (pinfunction "1_1") (pintype "passive"))
      (node (ref "C18") (pin "1") (pinfunction "1_1") (pintype "passive"))
      (node (ref "C2") (pin "1") (pinfunction "1_1") (pintype "passive"))
      (node (ref "C25") (pin "1") (pinfunction "1_1") (pintype "passive"))
      (node (ref "C26") (pin "2") (pinfunction "2_2") (pintype "passive"))
      (node (ref "C27") (pin "1") (pinfunction "1_1") (pintype "passive"))
      (node (ref "C28") (pin "1") (pinfunction "1_1") (pintype "passive"))
      (node (ref "C29") (pin "1") (pinfunction "1_1") (pintype "passive"))
      (node (ref "C3") (pin "1") (pinfunction "1_1") (pintype "passive"))
      (node (ref "C30") (pin "1") (pinfunction "1_1") (pintype "passive"))
      (node (ref "C31") (pin "1") (pinfunction "1_1") (pintype "passive"))
      (node (ref "C32") (pin "1") (pinfunction "1_1") (pintype "passive"))
      (node (ref "C33") (pin "2") (pinfunction "2_2") (pintype "passive"))
      (node (ref "C34") (pin "1") (pinfunction "1_1") (pintype "passive"))
      (node (ref "C35") (pin "1") (pinfunction "1_1") (pintype "passive"))
      (node (ref "C36") (pin "1") (pinfunction "1_1") (pintype "passive"))
      (node (ref "C37") (pin "1") (pinfunction "1_1") (pintype "passive"))
      (node (ref "C38") (pin "1") (pinfunction "1_1") (pintype "passive"))
      (node (ref "C39") (pin "2") (pinfunction "2_2") (pintype "passive"))
      (node (ref "C4") (pin "2") (pinfunction "2_2") (pintype "passive"))
      (node (ref "C41") (pin "1") (pinfunction "1_1") (pintype "passive"))
      (node (ref "C42") (pin "1") (pinfunction "1_1") (pintype "passive"))
      (node (ref "C43") (pin "1") (pinfunction "1_1") (pintype "passive"))
      (node (ref "C44") (pin "1") (pinfunction "1_1") (pintype "passive"))
      (node (ref "C45") (pin "1") (pinfunction "1_1") (pintype "passive"))
      (node (ref "C46") (pin "1") (pinfunction "1_1") (pintype "passive"))
      (node (ref "C47") (pin "2") (pinfunction "2_2") (pintype "passive"))
      (node (ref "C48") (pin "1") (pinfunction "1_1") (pintype "passive"))
      (node (ref "C49") (pin "1") (pinfunction "1_1") (pintype "passive"))
      (node (ref "C5") (pin "2") (pinfunction "2_2") (pintype "passive"))
      (node (ref "C50") (pin "1") (pinfunction "1_1") (pintype "passive"))
      (node (ref "C51") (pin "1") (pinfunction "1_1") (pintype "passive"))
      (node (ref "C52") (pin "1") (pinfunction "1_1") (pintype "passive"))
      (node (ref "C53") (pin "2") (pinfunction "2_2") (pintype "passive"))
      (node (ref "C54") (pin "1") (pinfunction "1_1") (pintype "passive"))
      (node (ref "C55") (pin "1") (pinfunction "1_1") (pintype "passive"))
      (node (ref "C56") (pin "1") (pinfunction "1_1") (pintype "passive"))
      (node (ref "C57") (pin "1") (pinfunction "1_1") (pintype "passive"))
      (node (ref "C58") (pin "1") (pinfunction "1_1") (pintype "passive"))
      (node (ref "C59") (pin "1") (pinfunction "1_1") (pintype "passive"))
      (node (ref "C6") (pin "1") (pinfunction "1_1") (pintype "passive"))
      (node (ref "C60") (pin "2") (pinfunction "2_2") (pintype "passive"))
      (node (ref "C61") (pin "1") (pinfunction "1_1") (pintype "passive"))
      (node (ref "C62") (pin "1") (pinfunction "1_1") (pintype "passive"))
      (node (ref "C63") (pin "1") (pinfunction "1_1") (pintype "passive"))
      (node (ref "C64") (pin "1") (pinfunction "1_1") (pintype "passive"))
      (node (ref "C65") (pin "1") (pinfunction "1_1") (pintype "passive"))
      (node (ref "C66") (pin "2") (pinfunction "2_2") (pintype "passive"))
      (node (ref "C67") (pin "1") (pinfunction "1_1") (pintype "passive"))
      (node (ref "C68") (pin "1") (pinfunction "1_1") (pintype "passive"))
      (node (ref "C69") (pin "1") (pinfunction "1_1") (pintype "passive"))
      (node (ref "C7") (pin "1") (pinfunction "1_1") (pintype "passive"))
      (node (ref "C70") (pin "1") (pinfunction "1_1") (pintype "passive"))
      (node (ref "C71") (pin "1") (pinfunction "1_1") (pintype "passive"))
      (node (ref "C72") (pin "1") (pinfunction "1_1") (pintype "passive"))
      (node (ref "C73") (pin "2") (pinfunction "2_2") (pintype "passive"))
      (node (ref "C74") (pin "1") (pinfunction "1_1") (pintype "passive"))
      (node (ref "C75") (pin "1") (pinfunction "1_1") (pintype "passive"))
      (node (ref "C76") (pin "1") (pinfunction "1_1") (pintype "passive"))
      (node (ref "C77") (pin "1") (pinfunction "1_1") (pintype "passive"))
      (node (ref "C78") (pin "1") (pinfunction "1_1") (pintype "passive"))
      (node (ref "C79") (pin "2") (pinfunction "2_2") (pintype "passive"))
      (node (ref "C8") (pin "1") (pinfunction "1_1") (pintype "passive"))
      (node (ref "C80") (pin "1") (pinfunction "1_1") (pintype "passive"))
      (node (ref "C81") (pin "1") (pinfunction "1_1") (pintype "passive"))
      (node (ref "C82") (pin "1") (pinfunction "1_1") (pintype "passive"))
      (node (ref "C83") (pin "1") (pinfunction "1_1") (pintype "passive"))
      (node (ref "C84") (pin "1") (pinfunction "1_1") (pintype "passive"))
      (node (ref "C85") (pin "1") (pinfunction "1_1") (pintype "passive"))
      (node (ref "C86") (pin "2") (pinfunction "2_2") (pintype "passive"))
      (node (ref "C87") (pin "1") (pinfunction "1_1") (pintype "passive"))
      (node (ref "C88") (pin "1") (pinfunction "1_1") (pintype "passive"))
      (node (ref "C89") (pin "1") (pinfunction "1_1") (pintype "passive"))
      (node (ref "C9") (pin "2") (pinfunction "2_2") (pintype "passive"))
      (node (ref "C90") (pin "1") (pinfunction "1_1") (pintype "passive"))
      (node (ref "C91") (pin "1") (pinfunction "1_1") (pintype "passive"))
      (node (ref "C92") (pin "2") (pinfunction "2_2") (pintype "passive"))
      (node (ref "C93") (pin "1") (pinfunction "1_1") (pintype "passive"))
      (node (ref "IC1") (pin "7") (pinfunction "VEE_7") (pintype "power_in"))
      (node (ref "IC1") (pin "8") (pinfunction "GND_8") (pintype "power_in"))
      (node (ref "IC11") (pin "7") (pinfunction "VEE_7") (pintype "power_in"))
      (node (ref "IC11") (pin "8") (pinfunction "GND_8") (pintype "power_in"))
      (node (ref "IC14") (pin "7") (pinfunction "VEE_7") (pintype "power_in"))
      (node (ref "IC14") (pin "8") (pinfunction "GND_8") (pintype "power_in"))
      (node (ref "IC17") (pin "7") (pinfunction "VEE_7") (pintype "power_in"))
      (node (ref "IC17") (pin "8") (pinfunction "GND_8") (pintype "power_in"))
      (node (ref "IC2") (pin "14") (pinfunction "RSTSEL_14") (pintype "bidirectional"))
      (node (ref "IC2") (pin "15") (pinfunction "~{ENABLE}_15") (pintype "bidirectional"))
      (node (ref "IC2") (pin "5") (pinfunction "VREF_L_5") (pintype "bidirectional"))
      (node (ref "IC2") (pin "6") (pinfunction "GND_6") (pintype "bidirectional"))
      (node (ref "IC20") (pin "7") (pinfunction "VEE_7") (pintype "power_in"))
      (node (ref "IC20") (pin "8") (pinfunction "GND_8") (pintype "power_in"))
      (node (ref "IC26") (pin "7") (pinfunction "VEE_7") (pintype "power_in"))
      (node (ref "IC26") (pin "8") (pinfunction "GND_8") (pintype "power_in"))
      (node (ref "IC5") (pin "2") (pinfunction "GND_2") (pintype "passive"))
      (node (ref "IC5") (pin "2@1") (pinfunction "GND_2@1") (pintype "passive"))
      (node (ref "IC7") (pin "7") (pinfunction "VEE_7") (pintype "power_in"))
      (node (ref "IC7") (pin "8") (pinfunction "GND_8") (pintype "power_in"))
      (node (ref "R2") (pin "1") (pinfunction "1_1") (pintype "passive"))
      (node (ref "R3") (pin "1") (pinfunction "1_1") (pintype "passive"))
      (node (ref "R5") (pin "1") (pinfunction "1_1") (pintype "passive"))
      (node (ref "R7") (pin "1") (pinfunction "1_1") (pintype "passive"))
      (node (ref "X6") (pin "14") (pinfunction "14_14") (pintype "passive"))
    )
    (net (code "10") (name "DAC_1") (class "Default")
      (node (ref "IC26") (pin "3") (pinfunction "X_3") (pintype "bidirectional"))
      (node (ref "R9") (pin "2") (pinfunction "2_2") (pintype "passive"))
    )
    (net (code "11") (name "DAC_2") (class "Default")
      (node (ref "IC17") (pin "3") (pinfunction "X_3") (pintype "bidirectional"))
      (node (ref "IC20") (pin "3") (pinfunction "X_3") (pintype "bidirectional"))
      (node (ref "R10") (pin "2") (pinfunction "2_2") (pintype "passive"))
    )
    (net (code "12") (name "DAC_3") (class "Default")
      (node (ref "IC14") (pin "3") (pinfunction "X_3") (pintype "bidirectional"))
      (node (ref "IC7") (pin "3") (pinfunction "X_3") (pintype "bidirectional"))
      (node (ref "R11") (pin "2") (pinfunction "2_2") (pintype "passive"))
    )
    (net (code "13") (name "DAC_4") (class "Default")
      (node (ref "IC1") (pin "3") (pinfunction "X_3") (pintype "bidirectional"))
      (node (ref "IC11") (pin "3") (pinfunction "X_3") (pintype "bidirectional"))
      (node (ref "R12") (pin "2") (pinfunction "2_2") (pintype "passive"))
    )
    (net (code "14") (name "DAC_RAW_1") (class "Default")
      (node (ref "IC2") (pin "1") (pinfunction "OUT_A_1") (pintype "bidirectional"))
      (node (ref "IC8") (pin "3") (pinfunction "+IN_3") (pintype "input"))
    )
    (net (code "15") (name "DAC_RAW_2") (class "Default")
      (node (ref "IC2") (pin "2") (pinfunction "OUT_B_2") (pintype "bidirectional"))
      (node (ref "IC8") (pin "5") (pinfunction "+IN_5") (pintype "input"))
    )
    (net (code "16") (name "DAC_RAW_3") (class "Default")
      (node (ref "IC2") (pin "7") (pinfunction "OUT_C_7") (pintype "bidirectional"))
      (node (ref "IC8") (pin "10") (pinfunction "+IN_10") (pintype "input"))
    )
    (net (code "17") (name "DAC_RAW_4") (class "Default")
      (node (ref "IC2") (pin "8") (pinfunction "OUT_D_8") (pintype "bidirectional"))
      (node (ref "IC8") (pin "12") (pinfunction "+IN_12") (pintype "input"))
    )
    (net (code "18") (name "INH_0") (class "Default")
      (node (ref "IC1") (pin "6") (pinfunction "INH_6") (pintype "input"))
      (node (ref "IC20") (pin "6") (pinfunction "INH_6") (pintype "input"))
      (node (ref "IC26") (pin "6") (pinfunction "INH_6") (pintype "input"))
      (node (ref "IC7") (pin "6") (pinfunction "INH_6") (pintype "input"))
      (node (ref "X6") (pin "3") (pinfunction "3_3") (pintype "passive"))
    )
    (net (code "19") (name "INH_1") (class "Default")
      (node (ref "IC11") (pin "6") (pinfunction "INH_6") (pintype "input"))
      (node (ref "IC14") (pin "6") (pinfunction "INH_6") (pintype "input"))
      (node (ref "IC17") (pin "6") (pinfunction "INH_6") (pintype "input"))
      (node (ref "X6") (pin "6") (pinfunction "6_6") (pintype "passive"))
    )
    (net (code "20") (name "IN_0") (class "Default")
      (node (ref "C13") (pin "2") (pinfunction "2_2") (pintype "passive"))
      (node (ref "IC1") (pin "13") (pinfunction "X0_13") (pintype "bidirectional"))
      (node (ref "IC3") (pin "12") (pinfunction "+IN_12") (pintype "input"))
    )
    (net (code "21") (name "IN_1") (class "Default")
      (node (ref "C12") (pin "2") (pinfunction "2_2") (pintype "passive"))
      (node (ref "IC1") (pin "14") (pinfunction "X1_14") (pintype "bidirectional"))
      (node (ref "IC3") (pin "10") (pinfunction "+IN_10") (pintype "input"))
    )
    (net (code "22") (name "IN_2") (class "Default")
      (node (ref "C11") (pin "2") (pinfunction "2_2") (pintype "passive"))
      (node (ref "IC1") (pin "15") (pinfunction "X2_15") (pintype "bidirectional"))
      (node (ref "IC3") (pin "5") (pinfunction "+IN_5") (pintype "input"))
    )
    (net (code "23") (name "IN_3") (class "Default")
      (node (ref "C7") (pin "2") (pinfunction "2_2") (pintype "passive"))
      (node (ref "IC1") (pin "12") (pinfunction "X3_12") (pintype "bidirectional"))
      (node (ref "IC3") (pin "3") (pinfunction "+IN_3") (pintype "input"))
    )
    (net (code "24") (name "IN_4") (class "Default")
      (node (ref "C25") (pin "2") (pinfunction "2_2") (pintype "passive"))
      (node (ref "IC1") (pin "1") (pinfunction "X4_1") (pintype "bidirectional"))
      (node (ref "IC6") (pin "12") (pinfunction "+IN_12") (pintype "input"))
    )
    (net (code "25") (name "IN_5") (class "Default")
      (node (ref "C18") (pin "2") (pinfunction "2_2") (pintype "passive"))
      (node (ref "IC1") (pin "5") (pinfunction "X5_5") (pintype "bidirectional"))
      (node (ref "IC6") (pin "10") (pinfunction "+IN_10") (pintype "input"))
    )
    (net (code "26") (name "IN_6") (class "Default")
      (node (ref "C17") (pin "2") (pinfunction "2_2") (pintype "passive"))
      (node (ref "IC1") (pin "2") (pinfunction "X6_2") (pintype "bidirectional"))
      (node (ref "IC6") (pin "5") (pinfunction "+IN_5") (pintype "input"))
    )
    (net (code "27") (name "IN_7") (class "Default")
      (node (ref "C16") (pin "2") (pinfunction "2_2") (pintype "passive"))
      (node (ref "IC1") (pin "4") (pinfunction "X7_4") (pintype "bidirectional"))
      (node (ref "IC6") (pin "3") (pinfunction "+IN_3") (pintype "input"))
    )
    (net (code "28") (name "IN_8") (class "Default")
      (node (ref "C46") (pin "2") (pinfunction "2_2") (pintype "passive"))
      (node (ref "IC11") (pin "13") (pinfunction "X0_13") (pintype "bidirectional"))
      (node (ref "IC12") (pin "12") (pinfunction "+IN_12") (pintype "input"))
    )
    (net (code "29") (name "IN_9") (class "Default")
      (node (ref "C45") (pin "2") (pinfunction "2_2") (pintype "passive"))
      (node (ref "IC11") (pin "14") (pinfunction "X1_14") (pintype "bidirectional"))
      (node (ref "IC12") (pin "10") (pinfunction "+IN_10") (pintype "input"))
    )
    (net (code "30") (name "IN_10") (class "Default")
      (node (ref "C44") (pin "2") (pinfunction "2_2") (pintype "passive"))
      (node (ref "IC11") (pin "15") (pinfunction "X2_15") (pintype "bidirectional"))
      (node (ref "IC12") (pin "5") (pinfunction "+IN_5") (pintype "input"))
    )
    (net (code "31") (name "IN_11") (class "Default")
      (node (ref "C43") (pin "2") (pinfunction "2_2") (pintype "passive"))
      (node (ref "IC11") (pin "12") (pinfunction "X3_12") (pintype "bidirectional"))
      (node (ref "IC12") (pin "3") (pinfunction "+IN_3") (pintype "input"))
    )
    (net (code "32") (name "IN_12") (class "Default")
      (node (ref "C52") (pin "2") (pinfunction "2_2") (pintype "passive"))
      (node (ref "IC11") (pin "1") (pinfunction "X4_1") (pintype "bidirectional"))
      (node (ref "IC13") (pin "12") (pinfunction "+IN_12") (pintype "input"))
    )
    (net (code "33") (name "IN_13") (class "Default")
      (node (ref "C51") (pin "2") (pinfunction "2_2") (pintype "passive"))
      (node (ref "IC11") (pin "5") (pinfunction "X5_5") (pintype "bidirectional"))
      (node (ref "IC13") (pin "10") (pinfunction "+IN_10") (pintype "input"))
    )
    (net (code "34") (name "IN_14") (class "Default")
      (node (ref "C50") (pin "2") (pinfunction "2_2") (pintype "passive"))
      (node (ref "IC11") (pin "2") (pinfunction "X6_2") (pintype "bidirectional"))
      (node (ref "IC13") (pin "5") (pinfunction "+IN_5") (pintype "input"))
    )
    (net (code "35") (name "IN_15") (class "Default")
      (node (ref "C49") (pin "2") (pinfunction "2_2") (pintype "passive"))
      (node (ref "IC11") (pin "4") (pinfunction "X7_4") (pintype "bidirectional"))
      (node (ref "IC13") (pin "3") (pinfunction "+IN_3") (pintype "input"))
    )
    (net (code "36") (name "IN_16") (class "Default")
      (node (ref "C32") (pin "2") (pinfunction "2_2") (pintype "passive"))
      (node (ref "IC7") (pin "13") (pinfunction "X0_13") (pintype "bidirectional"))
      (node (ref "IC9") (pin "12") (pinfunction "+IN_12") (pintype "input"))
    )
    (net (code "37") (name "IN_17") (class "Default")
      (node (ref "C31") (pin "2") (pinfunction "2_2") (pintype "passive"))
      (node (ref "IC7") (pin "14") (pinfunction "X1_14") (pintype "bidirectional"))
      (node (ref "IC9") (pin "10") (pinfunction "+IN_10") (pintype "input"))
    )
    (net (code "38") (name "IN_18") (class "Default")
      (node (ref "C30") (pin "2") (pinfunction "2_2") (pintype "passive"))
      (node (ref "IC7") (pin "15") (pinfunction "X2_15") (pintype "bidirectional"))
      (node (ref "IC9") (pin "5") (pinfunction "+IN_5") (pintype "input"))
    )
    (net (code "39") (name "IN_19") (class "Default")
      (node (ref "C29") (pin "2") (pinfunction "2_2") (pintype "passive"))
      (node (ref "IC7") (pin "12") (pinfunction "X3_12") (pintype "bidirectional"))
      (node (ref "IC9") (pin "3") (pinfunction "+IN_3") (pintype "input"))
    )
    (net (code "40") (name "IN_20") (class "Default")
      (node (ref "C38") (pin "2") (pinfunction "2_2") (pintype "passive"))
      (node (ref "IC10") (pin "12") (pinfunction "+IN_12") (pintype "input"))
      (node (ref "IC7") (pin "1") (pinfunction "X4_1") (pintype "bidirectional"))
    )
    (net (code "41") (name "IN_21") (class "Default")
      (node (ref "C37") (pin "2") (pinfunction "2_2") (pintype "passive"))
      (node (ref "IC10") (pin "10") (pinfunction "+IN_10") (pintype "input"))
      (node (ref "IC7") (pin "5") (pinfunction "X5_5") (pintype "bidirectional"))
    )
    (net (code "42") (name "IN_22") (class "Default")
      (node (ref "C36") (pin "2") (pinfunction "2_2") (pintype "passive"))
      (node (ref "IC10") (pin "5") (pinfunction "+IN_5") (pintype "input"))
      (node (ref "IC7") (pin "2") (pinfunction "X6_2") (pintype "bidirectional"))
    )
    (net (code "43") (name "IN_23") (class "Default")
      (node (ref "C35") (pin "2") (pinfunction "2_2") (pintype "passive"))
      (node (ref "IC10") (pin "3") (pinfunction "+IN_3") (pintype "input"))
      (node (ref "IC7") (pin "4") (pinfunction "X7_4") (pintype "bidirectional"))
    )
    (net (code "44") (name "IN_24") (class "Default")
      (node (ref "C59") (pin "2") (pinfunction "2_2") (pintype "passive"))
      (node (ref "IC14") (pin "13") (pinfunction "X0_13") (pintype "bidirectional"))
      (node (ref "IC15") (pin "12") (pinfunction "+IN_12") (pintype "input"))
    )
    (net (code "45") (name "IN_25") (class "Default")
      (node (ref "C58") (pin "2") (pinfunction "2_2") (pintype "passive"))
      (node (ref "IC14") (pin "14") (pinfunction "X1_14") (pintype "bidirectional"))
      (node (ref "IC15") (pin "10") (pinfunction "+IN_10") (pintype "input"))
    )
    (net (code "46") (name "IN_26") (class "Default")
      (node (ref "C57") (pin "2") (pinfunction "2_2") (pintype "passive"))
      (node (ref "IC14") (pin "15") (pinfunction "X2_15") (pintype "bidirectional"))
      (node (ref "IC15") (pin "5") (pinfunction "+IN_5") (pintype "input"))
    )
    (net (code "47") (name "IN_27") (class "Default")
      (node (ref "C56") (pin "2") (pinfunction "2_2") (pintype "passive"))
      (node (ref "IC14") (pin "12") (pinfunction "X3_12") (pintype "bidirectional"))
      (node (ref "IC15") (pin "3") (pinfunction "+IN_3") (pintype "input"))
    )
    (net (code "48") (name "IN_28") (class "Default")
      (node (ref "C65") (pin "2") (pinfunction "2_2") (pintype "passive"))
      (node (ref "IC14") (pin "1") (pinfunction "X4_1") (pintype "bidirectional"))
      (node (ref "IC16") (pin "12") (pinfunction "+IN_12") (pintype "input"))
    )
    (net (code "49") (name "IN_29") (class "Default")
      (node (ref "C64") (pin "2") (pinfunction "2_2") (pintype "passive"))
      (node (ref "IC14") (pin "5") (pinfunction "X5_5") (pintype "bidirectional"))
      (node (ref "IC16") (pin "10") (pinfunction "+IN_10") (pintype "input"))
    )
    (net (code "50") (name "IN_30") (class "Default")
      (node (ref "C63") (pin "2") (pinfunction "2_2") (pintype "passive"))
      (node (ref "IC14") (pin "2") (pinfunction "X6_2") (pintype "bidirectional"))
      (node (ref "IC16") (pin "5") (pinfunction "+IN_5") (pintype "input"))
    )
    (net (code "51") (name "IN_31") (class "Default")
      (node (ref "C62") (pin "2") (pinfunction "2_2") (pintype "passive"))
      (node (ref "IC14") (pin "4") (pinfunction "X7_4") (pintype "bidirectional"))
      (node (ref "IC16") (pin "3") (pinfunction "+IN_3") (pintype "input"))
    )
    (net (code "52") (name "IN_32") (class "Default")
      (node (ref "C85") (pin "2") (pinfunction "2_2") (pintype "passive"))
      (node (ref "IC20") (pin "13") (pinfunction "X0_13") (pintype "bidirectional"))
      (node (ref "IC21") (pin "12") (pinfunction "+IN_12") (pintype "input"))
    )
    (net (code "53") (name "IN_33") (class "Default")
      (node (ref "C84") (pin "2") (pinfunction "2_2") (pintype "passive"))
      (node (ref "IC20") (pin "14") (pinfunction "X1_14") (pintype "bidirectional"))
      (node (ref "IC21") (pin "10") (pinfunction "+IN_10") (pintype "input"))
    )
    (net (code "54") (name "IN_34") (class "Default")
      (node (ref "C83") (pin "2") (pinfunction "2_2") (pintype "passive"))
      (node (ref "IC20") (pin "15") (pinfunction "X2_15") (pintype "bidirectional"))
      (node (ref "IC21") (pin "5") (pinfunction "+IN_5") (pintype "input"))
    )
    (net (code "55") (name "IN_35") (class "Default")
      (node (ref "C82") (pin "2") (pinfunction "2_2") (pintype "passive"))
      (node (ref "IC20") (pin "12") (pinfunction "X3_12") (pintype "bidirectional"))
      (node (ref "IC21") (pin "3") (pinfunction "+IN_3") (pintype "input"))
    )
    (net (code "56") (name "IN_36") (class "Default")
      (node (ref "C91") (pin "2") (pinfunction "2_2") (pintype "passive"))
      (node (ref "IC20") (pin "1") (pinfunction "X4_1") (pintype "bidirectional"))
      (node (ref "IC22") (pin "12") (pinfunction "+IN_12") (pintype "input"))
    )
    (net (code "57") (name "IN_37") (class "Default")
      (node (ref "C90") (pin "2") (pinfunction "2_2") (pintype "passive"))
      (node (ref "IC20") (pin "5") (pinfunction "X5_5") (pintype "bidirectional"))
      (node (ref "IC22") (pin "10") (pinfunction "+IN_10") (pintype "input"))
    )
    (net (code "58") (name "IN_38") (class "Default")
      (node (ref "C89") (pin "2") (pinfunction "2_2") (pintype "passive"))
      (node (ref "IC20") (pin "2") (pinfunction "X6_2") (pintype "bidirectional"))
      (node (ref "IC22") (pin "5") (pinfunction "+IN_5") (pintype "input"))
    )
    (net (code "59") (name "IN_39") (class "Default")
      (node (ref "C88") (pin "2") (pinfunction "2_2") (pintype "passive"))
      (node (ref "IC20") (pin "4") (pinfunction "X7_4") (pintype "bidirectional"))
      (node (ref "IC22") (pin "3") (pinfunction "+IN_3") (pintype "input"))
    )
    (net (code "60") (name "IN_40") (class "Default")
      (node (ref "C72") (pin "2") (pinfunction "2_2") (pintype "passive"))
      (node (ref "IC17") (pin "13") (pinfunction "X0_13") (pintype "bidirectional"))
      (node (ref "IC18") (pin "12") (pinfunction "+IN_12") (pintype "input"))
    )
    (net (code "61") (name "IN_41") (class "Default")
      (node (ref "C71") (pin "2") (pinfunction "2_2") (pintype "passive"))
      (node (ref "IC17") (pin "14") (pinfunction "X1_14") (pintype "bidirectional"))
      (node (ref "IC18") (pin "10") (pinfunction "+IN_10") (pintype "input"))
    )
    (net (code "62") (name "IN_42") (class "Default")
      (node (ref "C70") (pin "2") (pinfunction "2_2") (pintype "passive"))
      (node (ref "IC17") (pin "15") (pinfunction "X2_15") (pintype "bidirectional"))
      (node (ref "IC18") (pin "5") (pinfunction "+IN_5") (pintype "input"))
    )
    (net (code "63") (name "IN_43") (class "Default")
      (node (ref "C69") (pin "2") (pinfunction "2_2") (pintype "passive"))
      (node (ref "IC17") (pin "12") (pinfunction "X3_12") (pintype "bidirectional"))
      (node (ref "IC18") (pin "3") (pinfunction "+IN_3") (pintype "input"))
    )
    (net (code "64") (name "IN_44") (class "Default")
      (node (ref "C78") (pin "2") (pinfunction "2_2") (pintype "passive"))
      (node (ref "IC17") (pin "1") (pinfunction "X4_1") (pintype "bidirectional"))
      (node (ref "IC19") (pin "12") (pinfunction "+IN_12") (pintype "input"))
    )
    (net (code "65") (name "IN_45") (class "Default")
      (node (ref "C77") (pin "2") (pinfunction "2_2") (pintype "passive"))
      (node (ref "IC17") (pin "5") (pinfunction "X5_5") (pintype "bidirectional"))
      (node (ref "IC19") (pin "10") (pinfunction "+IN_10") (pintype "input"))
    )
    (net (code "66") (name "IN_46") (class "Default")
      (node (ref "C76") (pin "2") (pinfunction "2_2") (pintype "passive"))
      (node (ref "IC17") (pin "2") (pinfunction "X6_2") (pintype "bidirectional"))
      (node (ref "IC19") (pin "5") (pinfunction "+IN_5") (pintype "input"))
    )
    (net (code "67") (name "IN_47") (class "Default")
      (node (ref "C75") (pin "2") (pinfunction "2_2") (pintype "passive"))
      (node (ref "IC17") (pin "4") (pinfunction "X7_4") (pintype "bidirectional"))
      (node (ref "IC19") (pin "3") (pinfunction "+IN_3") (pintype "input"))
    )
    (net (code "68") (name "IN_48") (class "Default")
      (node (ref "C111") (pin "2") (pinfunction "2_2") (pintype "passive"))
      (node (ref "IC26") (pin "13") (pinfunction "X0_13") (pintype "bidirectional"))
      (node (ref "IC27") (pin "12") (pinfunction "+IN_12") (pintype "input"))
    )
    (net (code "69") (name "IN_49") (class "Default")
      (node (ref "C110") (pin "2") (pinfunction "2_2") (pintype "passive"))
      (node (ref "IC26") (pin "14") (pinfunction "X1_14") (pintype "bidirectional"))
      (node (ref "IC27") (pin "10") (pinfunction "+IN_10") (pintype "input"))
    )
    (net (code "70") (name "IN_50") (class "Default")
      (node (ref "C109") (pin "2") (pinfunction "2_2") (pintype "passive"))
      (node (ref "IC26") (pin "15") (pinfunction "X2_15") (pintype "bidirectional"))
      (node (ref "IC27") (pin "5") (pinfunction "+IN_5") (pintype "input"))
    )
    (net (code "71") (name "IN_51") (class "Default")
      (node (ref "C108") (pin "2") (pinfunction "2_2") (pintype "passive"))
      (node (ref "IC26") (pin "12") (pinfunction "X3_12") (pintype "bidirectional"))
      (node (ref "IC27") (pin "3") (pinfunction "+IN_3") (pintype "input"))
    )
    (net (code "72") (name "IN_52") (class "Default")
      (node (ref "C117") (pin "2") (pinfunction "2_2") (pintype "passive"))
      (node (ref "IC26") (pin "1") (pinfunction "X4_1") (pintype "bidirectional"))
      (node (ref "IC28") (pin "12") (pinfunction "+IN_12") (pintype "input"))
    )
    (net (code "73") (name "IN_53") (class "Default")
      (node (ref "C116") (pin "2") (pinfunction "2_2") (pintype "passive"))
      (node (ref "IC26") (pin "5") (pinfunction "X5_5") (pintype "bidirectional"))
      (node (ref "IC28") (pin "10") (pinfunction "+IN_10") (pintype "input"))
    )
    (net (code "74") (name "IN_54") (class "Default")
      (node (ref "C115") (pin "2") (pinfunction "2_2") (pintype "passive"))
      (node (ref "IC26") (pin "2") (pinfunction "X6_2") (pintype "bidirectional"))
      (node (ref "IC28") (pin "5") (pinfunction "+IN_5") (pintype "input"))
    )
    (net (code "75") (name "IN_55") (class "Default")
      (node (ref "C114") (pin "2") (pinfunction "2_2") (pintype "passive"))
      (node (ref "IC26") (pin "4") (pinfunction "X7_4") (pintype "bidirectional"))
      (node (ref "IC28") (pin "3") (pinfunction "+IN_3") (pintype "input"))
    )
    (net (code "76") (name "LDAC") (class "Default")
      (node (ref "IC2") (pin "16") (pinfunction "LDAC_16") (pintype "bidirectional"))
      (node (ref "X6") (pin "9") (pinfunction "9_9") (pintype "passive"))
    )
    (net (code "77") (name "Net-(IC2-IOVDD)") (class "Default")
      (node (ref "C9") (pin "1") (pinfunction "1_1") (pintype "passive"))
      (node (ref "IC2") (pin "12") (pinfunction "IOVDD_12") (pintype "power_in"))
      (node (ref "JP1") (pin "2") (pinfunction "2_2") (pintype "passive"))
    )
    (net (code "78") (name "Net-(IC8A--IN)") (class "Default")
      (node (ref "IC8") (pin "2") (pinfunction "-IN_2") (pintype "input"))
      (node (ref "R1") (pin "1") (pinfunction "1_1") (pintype "passive"))
      (node (ref "R2") (pin "2") (pinfunction "2_2") (pintype "passive"))
    )
    (net (code "79") (name "Net-(IC8A-OUT)") (class "Default")
      (node (ref "IC8") (pin "1") (pinfunction "OUT_1") (pintype "output"))
      (node (ref "R1") (pin "2") (pinfunction "2_2") (pintype "passive"))
      (node (ref "R9") (pin "1") (pinfunction "1_1") (pintype "passive"))
    )
    (net (code "80") (name "Net-(IC8B--IN)") (class "Default")
      (node (ref "IC8") (pin "6") (pinfunction "-IN_6") (pintype "input"))
      (node (ref "R3") (pin "2") (pinfunction "2_2") (pintype "passive"))
      (node (ref "R4") (pin "1") (pinfunction "1_1") (pintype "passive"))
    )
    (net (code "81") (name "Net-(IC8B-OUT)") (class "Default")
      (node (ref "IC8") (pin "7") (pinfunction "OUT_7") (pintype "output"))
      (node (ref "R10") (pin "1") (pinfunction "1_1") (pintype "passive"))
      (node (ref "R4") (pin "2") (pinfunction "2_2") (pintype "passive"))
    )
    (net (code "82") (name "Net-(IC8C--IN)") (class "Default")
      (node (ref "IC8") (pin "9") (pinfunction "-IN_9") (pintype "input"))
      (node (ref "R5") (pin "2") (pinfunction "2_2") (pintype "passive"))
      (node (ref "R6") (pin "1") (pinfunction "1_1") (pintype "passive"))
    )
    (net (code "83") (name "Net-(IC8C-OUT)") (class "Default")
      (node (ref "IC8") (pin "8") (pinfunction "OUT_8") (pintype "output"))
      (node (ref "R11") (pin "1") (pinfunction "1_1") (pintype "passive"))
      (node (ref "R6") (pin "2") (pinfunction "2_2") (pintype "passive"))
    )
    (net (code "84") (name "Net-(IC8D--IN)") (class "Default")
      (node (ref "IC8") (pin "13") (pinfunction "-IN_13") (pintype "input"))
      (node (ref "R7") (pin "2") (pinfunction "2_2") (pintype "passive"))
      (node (ref "R8") (pin "1") (pinfunction "1_1") (pintype "passive"))
    )
    (net (code "85") (name "Net-(IC8D-OUT)") (class "Default")
      (node (ref "IC8") (pin "14") (pinfunction "OUT_14") (pintype "output"))
      (node (ref "R12") (pin "1") (pinfunction "1_1") (pintype "passive"))
      (node (ref "R8") (pin "2") (pinfunction "2_2") (pintype "passive"))
    )
    (net (code "86") (name "OUT_0") (class "Default")
      (node (ref "IC3") (pin "13") (pinfunction "-IN_13") (pintype "input"))
      (node (ref "IC3") (pin "14") (pinfunction "OUT_14") (pintype "output"))
      (node (ref "U$2") (pin "1") (pinfunction "1_1") (pintype "passive"))
      (node (ref "U$2") (pin "2") (pinfunction "2_2") (pintype "passive"))
    )
    (net (code "87") (name "OUT_1") (class "Default")
      (node (ref "IC3") (pin "8") (pinfunction "OUT_8") (pintype "output"))
      (node (ref "IC3") (pin "9") (pinfunction "-IN_9") (pintype "input"))
      (node (ref "U$2") (pin "3") (pinfunction "3_3") (pintype "passive"))
      (node (ref "U$2") (pin "4") (pinfunction "4_4") (pintype "passive"))
    )
    (net (code "88") (name "OUT_2") (class "Default")
      (node (ref "IC3") (pin "6") (pinfunction "-IN_6") (pintype "input"))
      (node (ref "IC3") (pin "7") (pinfunction "OUT_7") (pintype "output"))
      (node (ref "U$2") (pin "5") (pinfunction "5_5") (pintype "passive"))
      (node (ref "U$2") (pin "6") (pinfunction "6_6") (pintype "passive"))
    )
    (net (code "89") (name "OUT_3") (class "Default")
      (node (ref "IC3") (pin "1") (pinfunction "OUT_1") (pintype "output"))
      (node (ref "IC3") (pin "2") (pinfunction "-IN_2") (pintype "input"))
      (node (ref "U$2") (pin "7") (pinfunction "7_7") (pintype "passive"))
      (node (ref "U$2") (pin "8") (pinfunction "8_8") (pintype "passive"))
    )
    (net (code "90") (name "OUT_4") (class "Default")
      (node (ref "IC6") (pin "13") (pinfunction "-IN_13") (pintype "input"))
      (node (ref "IC6") (pin "14") (pinfunction "OUT_14") (pintype "output"))
      (node (ref "U$2") (pin "10") (pinfunction "10_10") (pintype "passive"))
      (node (ref "U$2") (pin "9") (pinfunction "9_9") (pintype "passive"))
    )
    (net (code "91") (name "OUT_5") (class "Default")
      (node (ref "IC6") (pin "8") (pinfunction "OUT_8") (pintype "output"))
      (node (ref "IC6") (pin "9") (pinfunction "-IN_9") (pintype "input"))
      (node (ref "U$2") (pin "11") (pinfunction "11_11") (pintype "passive"))
      (node (ref "U$2") (pin "12") (pinfunction "12_12") (pintype "passive"))
    )
    (net (code "92") (name "OUT_6") (class "Default")
      (node (ref "IC6") (pin "6") (pinfunction "-IN_6") (pintype "input"))
      (node (ref "IC6") (pin "7") (pinfunction "OUT_7") (pintype "output"))
      (node (ref "U$2") (pin "13") (pinfunction "13_13") (pintype "passive"))
      (node (ref "U$2") (pin "14") (pinfunction "14_14") (pintype "passive"))
    )
    (net (code "93") (name "OUT_7") (class "Default")
      (node (ref "IC6") (pin "1") (pinfunction "OUT_1") (pintype "output"))
      (node (ref "IC6") (pin "2") (pinfunction "-IN_2") (pintype "input"))
      (node (ref "U$2") (pin "15") (pinfunction "15_15") (pintype "passive"))
      (node (ref "U$2") (pin "16") (pinfunction "16_16") (pintype "passive"))
    )
    (net (code "94") (name "OUT_8") (class "Default")
      (node (ref "IC12") (pin "13") (pinfunction "-IN_13") (pintype "input"))
      (node (ref "IC12") (pin "14") (pinfunction "OUT_14") (pintype "output"))
      (node (ref "U$2") (pin "17") (pinfunction "17_17") (pintype "passive"))
      (node (ref "U$2") (pin "18") (pinfunction "18_18") (pintype "passive"))
    )
    (net (code "95") (name "OUT_9") (class "Default")
      (node (ref "IC12") (pin "8") (pinfunction "OUT_8") (pintype "output"))
      (node (ref "IC12") (pin "9") (pinfunction "-IN_9") (pintype "input"))
      (node (ref "U$2") (pin "19") (pinfunction "19_19") (pintype "passive"))
      (node (ref "U$2") (pin "20") (pinfunction "20_20") (pintype "passive"))
    )
    (net (code "96") (name "OUT_10") (class "Default")
      (node (ref "IC12") (pin "6") (pinfunction "-IN_6") (pintype "input"))
      (node (ref "IC12") (pin "7") (pinfunction "OUT_7") (pintype "output"))
      (node (ref "U$2") (pin "21") (pinfunction "21_21") (pintype "passive"))
      (node (ref "U$2") (pin "22") (pinfunction "22_22") (pintype "passive"))
    )
    (net (code "97") (name "OUT_11") (class "Default")
      (node (ref "IC12") (pin "1") (pinfunction "OUT_1") (pintype "output"))
      (node (ref "IC12") (pin "2") (pinfunction "-IN_2") (pintype "input"))
      (node (ref "U$2") (pin "23") (pinfunction "23_23") (pintype "passive"))
      (node (ref "U$2") (pin "24") (pinfunction "24_24") (pintype "passive"))
    )
    (net (code "98") (name "OUT_12") (class "Default")
      (node (ref "IC13") (pin "13") (pinfunction "-IN_13") (pintype "input"))
      (node (ref "IC13") (pin "14") (pinfunction "OUT_14") (pintype "output"))
      (node (ref "U$2") (pin "25") (pinfunction "25_25") (pintype "passive"))
      (node (ref "U$2") (pin "26") (pinfunction "26_26") (pintype "passive"))
    )
    (net (code "99") (name "OUT_13") (class "Default")
      (node (ref "IC13") (pin "8") (pinfunction "OUT_8") (pintype "output"))
      (node (ref "IC13") (pin "9") (pinfunction "-IN_9") (pintype "input"))
      (node (ref "U$2") (pin "27") (pinfunction "27_27") (pintype "passive"))
      (node (ref "U$2") (pin "28") (pinfunction "28_28") (pintype "passive"))
    )
    (net (code "100") (name "OUT_14") (class "Default")
      (node (ref "IC13") (pin "6") (pinfunction "-IN_6") (pintype "input"))
      (node (ref "IC13") (pin "7") (pinfunction "OUT_7") (pintype "output"))
      (node (ref "U$2") (pin "29") (pinfunction "29_29") (pintype "passive"))
      (node (ref "U$2") (pin "30") (pinfunction "30_30") (pintype "passive"))
    )
    (net (code "101") (name "OUT_15") (class "Default")
      (node (ref "IC13") (pin "1") (pinfunction "OUT_1") (pintype "output"))
      (node (ref "IC13") (pin "2") (pinfunction "-IN_2") (pintype "input"))
      (node (ref "X5") (pin "1") (pinfunction "1_1") (pintype "passive"))
    )
    (net (code "102") (name "OUT_16") (class "Default")
      (node (ref "IC9") (pin "13") (pinfunction "-IN_13") (pintype "input"))
      (node (ref "IC9") (pin "14") (pinfunction "OUT_14") (pintype "output"))
      (node (ref "U$3") (pin "1") (pinfunction "1_1") (pintype "passive"))
      (node (ref "U$3") (pin "2") (pinfunction "2_2") (pintype "passive"))
    )
    (net (code "103") (name "OUT_17") (class "Default")
      (node (ref "IC9") (pin "8") (pinfunction "OUT_8") (pintype "output"))
      (node (ref "IC9") (pin "9") (pinfunction "-IN_9") (pintype "input"))
      (node (ref "U$3") (pin "3") (pinfunction "3_3") (pintype "passive"))
      (node (ref "U$3") (pin "4") (pinfunction "4_4") (pintype "passive"))
    )
    (net (code "104") (name "OUT_18") (class "Default")
      (node (ref "IC9") (pin "6") (pinfunction "-IN_6") (pintype "input"))
      (node (ref "IC9") (pin "7") (pinfunction "OUT_7") (pintype "output"))
      (node (ref "U$3") (pin "5") (pinfunction "5_5") (pintype "passive"))
      (node (ref "U$3") (pin "6") (pinfunction "6_6") (pintype "passive"))
    )
    (net (code "105") (name "OUT_19") (class "Default")
      (node (ref "IC9") (pin "1") (pinfunction "OUT_1") (pintype "output"))
      (node (ref "IC9") (pin "2") (pinfunction "-IN_2") (pintype "input"))
      (node (ref "U$3") (pin "7") (pinfunction "7_7") (pintype "passive"))
      (node (ref "U$3") (pin "8") (pinfunction "8_8") (pintype "passive"))
    )
    (net (code "106") (name "OUT_20") (class "Default")
      (node (ref "IC10") (pin "13") (pinfunction "-IN_13") (pintype "input"))
      (node (ref "IC10") (pin "14") (pinfunction "OUT_14") (pintype "output"))
      (node (ref "U$3") (pin "10") (pinfunction "10_10") (pintype "passive"))
      (node (ref "U$3") (pin "9") (pinfunction "9_9") (pintype "passive"))
    )
    (net (code "107") (name "OUT_21") (class "Default")
      (node (ref "IC10") (pin "8") (pinfunction "OUT_8") (pintype "output"))
      (node (ref "IC10") (pin "9") (pinfunction "-IN_9") (pintype "input"))
      (node (ref "U$3") (pin "11") (pinfunction "11_11") (pintype "passive"))
      (node (ref "U$3") (pin "12") (pinfunction "12_12") (pintype "passive"))
    )
    (net (code "108") (name "OUT_22") (class "Default")
      (node (ref "IC10") (pin "6") (pinfunction "-IN_6") (pintype "input"))
      (node (ref "IC10") (pin "7") (pinfunction "OUT_7") (pintype "output"))
      (node (ref "U$3") (pin "13") (pinfunction "13_13") (pintype "passive"))
      (node (ref "U$3") (pin "14") (pinfunction "14_14") (pintype "passive"))
    )
    (net (code "109") (name "OUT_23") (class "Default")
      (node (ref "IC10") (pin "1") (pinfunction "OUT_1") (pintype "output"))
      (node (ref "IC10") (pin "2") (pinfunction "-IN_2") (pintype "input"))
      (node (ref "U$3") (pin "15") (pinfunction "15_15") (pintype "passive"))
      (node (ref "U$3") (pin "16") (pinfunction "16_16") (pintype "passive"))
    )
    (net (code "110") (name "OUT_24") (class "Default")
      (node (ref "IC15") (pin "13") (pinfunction "-IN_13") (pintype "input"))
      (node (ref "IC15") (pin "14") (pinfunction "OUT_14") (pintype "output"))
      (node (ref "U$3") (pin "17") (pinfunction "17_17") (pintype "passive"))
      (node (ref "U$3") (pin "18") (pinfunction "18_18") (pintype "passive"))
    )
    (net (code "111") (name "OUT_25") (class "Default")
      (node (ref "IC15") (pin "8") (pinfunction "OUT_8") (pintype "output"))
      (node (ref "IC15") (pin "9") (pinfunction "-IN_9") (pintype "input"))
      (node (ref "U$3") (pin "19") (pinfunction "19_19") (pintype "passive"))
      (node (ref "U$3") (pin "20") (pinfunction "20_20") (pintype "passive"))
    )
    (net (code "112") (name "OUT_26") (class "Default")
      (node (ref "IC15") (pin "6") (pinfunction "-IN_6") (pintype "input"))
      (node (ref "IC15") (pin "7") (pinfunction "OUT_7") (pintype "output"))
      (node (ref "U$3") (pin "21") (pinfunction "21_21") (pintype "passive"))
      (node (ref "U$3") (pin "22") (pinfunction "22_22") (pintype "passive"))
    )
    (net (code "113") (name "OUT_27") (class "Default")
      (node (ref "IC15") (pin "1") (pinfunction "OUT_1") (pintype "output"))
      (node (ref "IC15") (pin "2") (pinfunction "-IN_2") (pintype "input"))
      (node (ref "U$3") (pin "23") (pinfunction "23_23") (pintype "passive"))
      (node (ref "U$3") (pin "24") (pinfunction "24_24") (pintype "passive"))
    )
    (net (code "114") (name "OUT_28") (class "Default")
      (node (ref "IC16") (pin "13") (pinfunction "-IN_13") (pintype "input"))
      (node (ref "IC16") (pin "14") (pinfunction "OUT_14") (pintype "output"))
      (node (ref "U$3") (pin "25") (pinfunction "25_25") (pintype "passive"))
      (node (ref "U$3") (pin "26") (pinfunction "26_26") (pintype "passive"))
    )
    (net (code "115") (name "OUT_29") (class "Default")
      (node (ref "IC16") (pin "8") (pinfunction "OUT_8") (pintype "output"))
      (node (ref "IC16") (pin "9") (pinfunction "-IN_9") (pintype "input"))
      (node (ref "U$3") (pin "27") (pinfunction "27_27") (pintype "passive"))
      (node (ref "U$3") (pin "28") (pinfunction "28_28") (pintype "passive"))
    )
    (net (code "116") (name "OUT_30") (class "Default")
      (node (ref "IC16") (pin "6") (pinfunction "-IN_6") (pintype "input"))
      (node (ref "IC16") (pin "7") (pinfunction "OUT_7") (pintype "output"))
      (node (ref "U$3") (pin "29") (pinfunction "29_29") (pintype "passive"))
      (node (ref "U$3") (pin "30") (pinfunction "30_30") (pintype "passive"))
    )
    (net (code "117") (name "OUT_31") (class "Default")
      (node (ref "IC16") (pin "1") (pinfunction "OUT_1") (pintype "output"))
      (node (ref "IC16") (pin "2") (pinfunction "-IN_2") (pintype "input"))
      (node (ref "X9") (pin "1") (pinfunction "1_1") (pintype "passive"))
    )
    (net (code "118") (name "OUT_32") (class "Default")
      (node (ref "IC21") (pin "13") (pinfunction "-IN_13") (pintype "input"))
      (node (ref "IC21") (pin "14") (pinfunction "OUT_14") (pintype "output"))
      (node (ref "X9") (pin "2") (pinfunction "2_2") (pintype "passive"))
    )
    (net (code "119") (name "OUT_33") (class "Default")
      (node (ref "IC21") (pin "8") (pinfunction "OUT_8") (pintype "output"))
      (node (ref "IC21") (pin "9") (pinfunction "-IN_9") (pintype "input"))
      (node (ref "X10") (pin "1") (pinfunction "1_1") (pintype "passive"))
      (node (ref "X10") (pin "2") (pinfunction "2_2") (pintype "passive"))
    )
    (net (code "120") (name "OUT_34") (class "Default")
      (node (ref "IC21") (pin "6") (pinfunction "-IN_6") (pintype "input"))
      (node (ref "IC21") (pin "7") (pinfunction "OUT_7") (pintype "output"))
      (node (ref "X10") (pin "3") (pinfunction "3_3") (pintype "passive"))
      (node (ref "X10") (pin "4") (pinfunction "4_4") (pintype "passive"))
    )
    (net (code "121") (name "OUT_35") (class "Default")
      (node (ref "IC21") (pin "1") (pinfunction "OUT_1") (pintype "output"))
      (node (ref "IC21") (pin "2") (pinfunction "-IN_2") (pintype "input"))
      (node (ref "X10") (pin "5") (pinfunction "5_5") (pintype "passive"))
      (node (ref "X10") (pin "6") (pinfunction "6_6") (pintype "passive"))
    )
    (net (code "122") (name "OUT_36") (class "Default")
      (node (ref "IC22") (pin "13") (pinfunction "-IN_13") (pintype "input"))
      (node (ref "IC22") (pin "14") (pinfunction "OUT_14") (pintype "output"))
      (node (ref "X10") (pin "7") (pinfunction "7_7") (pintype "passive"))
      (node (ref "X10") (pin "8") (pinfunction "8_8") (pintype "passive"))
    )
    (net (code "123") (name "OUT_37") (class "Default")
      (node (ref "IC22") (pin "8") (pinfunction "OUT_8") (pintype "output"))
      (node (ref "IC22") (pin "9") (pinfunction "-IN_9") (pintype "input"))
      (node (ref "X10") (pin "10") (pinfunction "10_10") (pintype "passive"))
      (node (ref "X10") (pin "9") (pinfunction "9_9") (pintype "passive"))
    )
    (net (code "124") (name "OUT_38") (class "Default")
      (node (ref "IC22") (pin "6") (pinfunction "-IN_6") (pintype "input"))
      (node (ref "IC22") (pin "7") (pinfunction "OUT_7") (pintype "output"))
      (node (ref "X10") (pin "11") (pinfunction "11_11") (pintype "passive"))
      (node (ref "X10") (pin "12") (pinfunction "12_12") (pintype "passive"))
    )
    (net (code "125") (name "OUT_39") (class "Default")
      (node (ref "IC22") (pin "1") (pinfunction "OUT_1") (pintype "output"))
      (node (ref "IC22") (pin "2") (pinfunction "-IN_2") (pintype "input"))
      (node (ref "X10") (pin "13") (pinfunction "13_13") (pintype "passive"))
      (node (ref "X10") (pin "14") (pinfunction "14_14") (pintype "passive"))
    )
    (net (code "126") (name "OUT_40") (class "Default")
      (node (ref "IC18") (pin "13") (pinfunction "-IN_13") (pintype "input"))
      (node (ref "IC18") (pin "14") (pinfunction "OUT_14") (pintype "output"))
      (node (ref "X4") (pin "1") (pinfunction "1_1") (pintype "passive"))
    )
    (net (code "127") (name "OUT_41") (class "Default")
      (node (ref "IC18") (pin "8") (pinfunction "OUT_8") (pintype "output"))
      (node (ref "IC18") (pin "9") (pinfunction "-IN_9") (pintype "input"))
      (node (ref "U$4") (pin "1") (pinfunction "1_1") (pintype "passive"))
      (node (ref "U$4") (pin "2") (pinfunction "2_2") (pintype "passive"))
    )
    (net (code "128") (name "OUT_42") (class "Default")
      (node (ref "IC18") (pin "6") (pinfunction "-IN_6") (pintype "input"))
      (node (ref "IC18") (pin "7") (pinfunction "OUT_7") (pintype "output"))
      (node (ref "U$4") (pin "3") (pinfunction "3_3") (pintype "passive"))
      (node (ref "U$4") (pin "4") (pinfunction "4_4") (pintype "passive"))
    )
    (net (code "129") (name "OUT_43") (class "Default")
      (node (ref "IC18") (pin "1") (pinfunction "OUT_1") (pintype "output"))
      (node (ref "IC18") (pin "2") (pinfunction "-IN_2") (pintype "input"))
      (node (ref "U$4") (pin "5") (pinfunction "5_5") (pintype "passive"))
      (node (ref "U$4") (pin "6") (pinfunction "6_6") (pintype "passive"))
    )
    (net (code "130") (name "OUT_44") (class "Default")
      (node (ref "IC19") (pin "13") (pinfunction "-IN_13") (pintype "input"))
      (node (ref "IC19") (pin "14") (pinfunction "OUT_14") (pintype "output"))
      (node (ref "U$4") (pin "7") (pinfunction "7_7") (pintype "passive"))
      (node (ref "U$4") (pin "8") (pinfunction "8_8") (pintype "passive"))
    )
    (net (code "131") (name "OUT_45") (class "Default")
      (node (ref "IC19") (pin "8") (pinfunction "OUT_8") (pintype "output"))
      (node (ref "IC19") (pin "9") (pinfunction "-IN_9") (pintype "input"))
      (node (ref "U$4") (pin "10") (pinfunction "10_10") (pintype "passive"))
      (node (ref "U$4") (pin "9") (pinfunction "9_9") (pintype "passive"))
    )
    (net (code "132") (name "OUT_46") (class "Default")
      (node (ref "IC19") (pin "6") (pinfunction "-IN_6") (pintype "input"))
      (node (ref "IC19") (pin "7") (pinfunction "OUT_7") (pintype "output"))
      (node (ref "U$4") (pin "11") (pinfunction "11_11") (pintype "passive"))
      (node (ref "U$4") (pin "12") (pinfunction "12_12") (pintype "passive"))
    )
    (net (code "133") (name "OUT_47") (class "Default")
      (node (ref "IC19") (pin "1") (pinfunction "OUT_1") (pintype "output"))
      (node (ref "IC19") (pin "2") (pinfunction "-IN_2") (pintype "input"))
      (node (ref "U$4") (pin "13") (pinfunction "13_13") (pintype "passive"))
      (node (ref "U$4") (pin "14") (pinfunction "14_14") (pintype "passive"))
    )
    (net (code "134") (name "OUT_48") (class "Default")
      (node (ref "IC27") (pin "13") (pinfunction "-IN_13") (pintype "input"))
      (node (ref "IC27") (pin "14") (pinfunction "OUT_14") (pintype "output"))
      (node (ref "U$4") (pin "15") (pinfunction "15_15") (pintype "passive"))
      (node (ref "U$4") (pin "16") (pinfunction "16_16") (pintype "passive"))
    )
    (net (code "135") (name "OUT_49") (class "Default")
      (node (ref "IC27") (pin "8") (pinfunction "OUT_8") (pintype "output"))
      (node (ref "IC27") (pin "9") (pinfunction "-IN_9") (pintype "input"))
      (node (ref "U$4") (pin "17") (pinfunction "17_17") (pintype "passive"))
      (node (ref "U$4") (pin "18") (pinfunction "18_18") (pintype "passive"))
    )
    (net (code "136") (name "OUT_50") (class "Default")
      (node (ref "IC27") (pin "6") (pinfunction "-IN_6") (pintype "input"))
      (node (ref "IC27") (pin "7") (pinfunction "OUT_7") (pintype "output"))
      (node (ref "U$4") (pin "19") (pinfunction "19_19") (pintype "passive"))
      (node (ref "U$4") (pin "20") (pinfunction "20_20") (pintype "passive"))
    )
    (net (code "137") (name "OUT_51") (class "Default")
      (node (ref "IC27") (pin "1") (pinfunction "OUT_1") (pintype "output"))
      (node (ref "IC27") (pin "2") (pinfunction "-IN_2") (pintype "input"))
      (node (ref "U$4") (pin "21") (pinfunction "21_21") (pintype "passive"))
      (node (ref "U$4") (pin "22") (pinfunction "22_22") (pintype "passive"))
    )
    (net (code "138") (name "OUT_52") (class "Default")
      (node (ref "IC28") (pin "13") (pinfunction "-IN_13") (pintype "input"))
      (node (ref "IC28") (pin "14") (pinfunction "OUT_14") (pintype "output"))
      (node (ref "U$4") (pin "23") (pinfunction "23_23") (pintype "passive"))
      (node (ref "U$4") (pin "24") (pinfunction "24_24") (pintype "passive"))
    )
    (net (code "139") (name "OUT_53") (class "Default")
      (node (ref "IC28") (pin "8") (pinfunction "OUT_8") (pintype "output"))
      (node (ref "IC28") (pin "9") (pinfunction "-IN_9") (pintype "input"))
      (node (ref "U$4") (pin "25") (pinfunction "25_25") (pintype "passive"))
      (node (ref "U$4") (pin "26") (pinfunction "26_26") (pintype "passive"))
    )
    (net (code "140") (name "OUT_54") (class "Default")
      (node (ref "IC28") (pin "6") (pinfunction "-IN_6") (pintype "input"))
      (node (ref "IC28") (pin "7") (pinfunction "OUT_7") (pintype "output"))
      (node (ref "U$4") (pin "27") (pinfunction "27_27") (pintype "passive"))
      (node (ref "U$4") (pin "28") (pinfunction "28_28") (pintype "passive"))
    )
    (net (code "141") (name "OUT_55") (class "Default")
      (node (ref "IC28") (pin "1") (pinfunction "OUT_1") (pintype "output"))
      (node (ref "IC28") (pin "2") (pinfunction "-IN_2") (pintype "input"))
      (node (ref "U$4") (pin "29") (pinfunction "29_29") (pintype "passive"))
      (node (ref "U$4") (pin "30") (pinfunction "30_30") (pintype "passive"))
    )
    (net (code "142") (name "SCK") (class "Default")
      (node (ref "IC2") (pin "10") (pinfunction "SCLK_10") (pintype "bidirectional"))
      (node (ref "X6") (pin "7") (pinfunction "7_7") (pintype "passive"))
    )
    (net (code "143") (name "SDA") (class "Default")
      (node (ref "IC2") (pin "11") (pinfunction "DIN_11") (pintype "bidirectional"))
      (node (ref "X6") (pin "8") (pinfunction "8_8") (pintype "passive"))
    )
    (net (code "144") (name "unconnected-(X6-Pad5)") (class "Default")
      (node (ref "X6") (pin "5") (pinfunction "5_5") (pintype "passive"))
    )
    (net (code "145") (name "unconnected-(X6-Pad12)") (class "Default")
      (node (ref "X6") (pin "12") (pinfunction "12_12") (pintype "passive"))
    )
    (net (code "146") (name "unconnected-(X6-Pad13)") (class "Default")
      (node (ref "X6") (pin "13") (pinfunction "13_13") (pintype "passive"))
    )
    (net (code "147") (name "~{SYNC}") (class "Default")
      (node (ref "IC2") (pin "9") (pinfunction "~{SYNC}_9") (pintype "bidirectional"))
      (node (ref "X6") (pin "10") (pinfunction "10_10") (pintype "passive"))
    )
  )
)
